# io-board-b-1.net
KiCad netlist of a schematic drawn in EAGLE
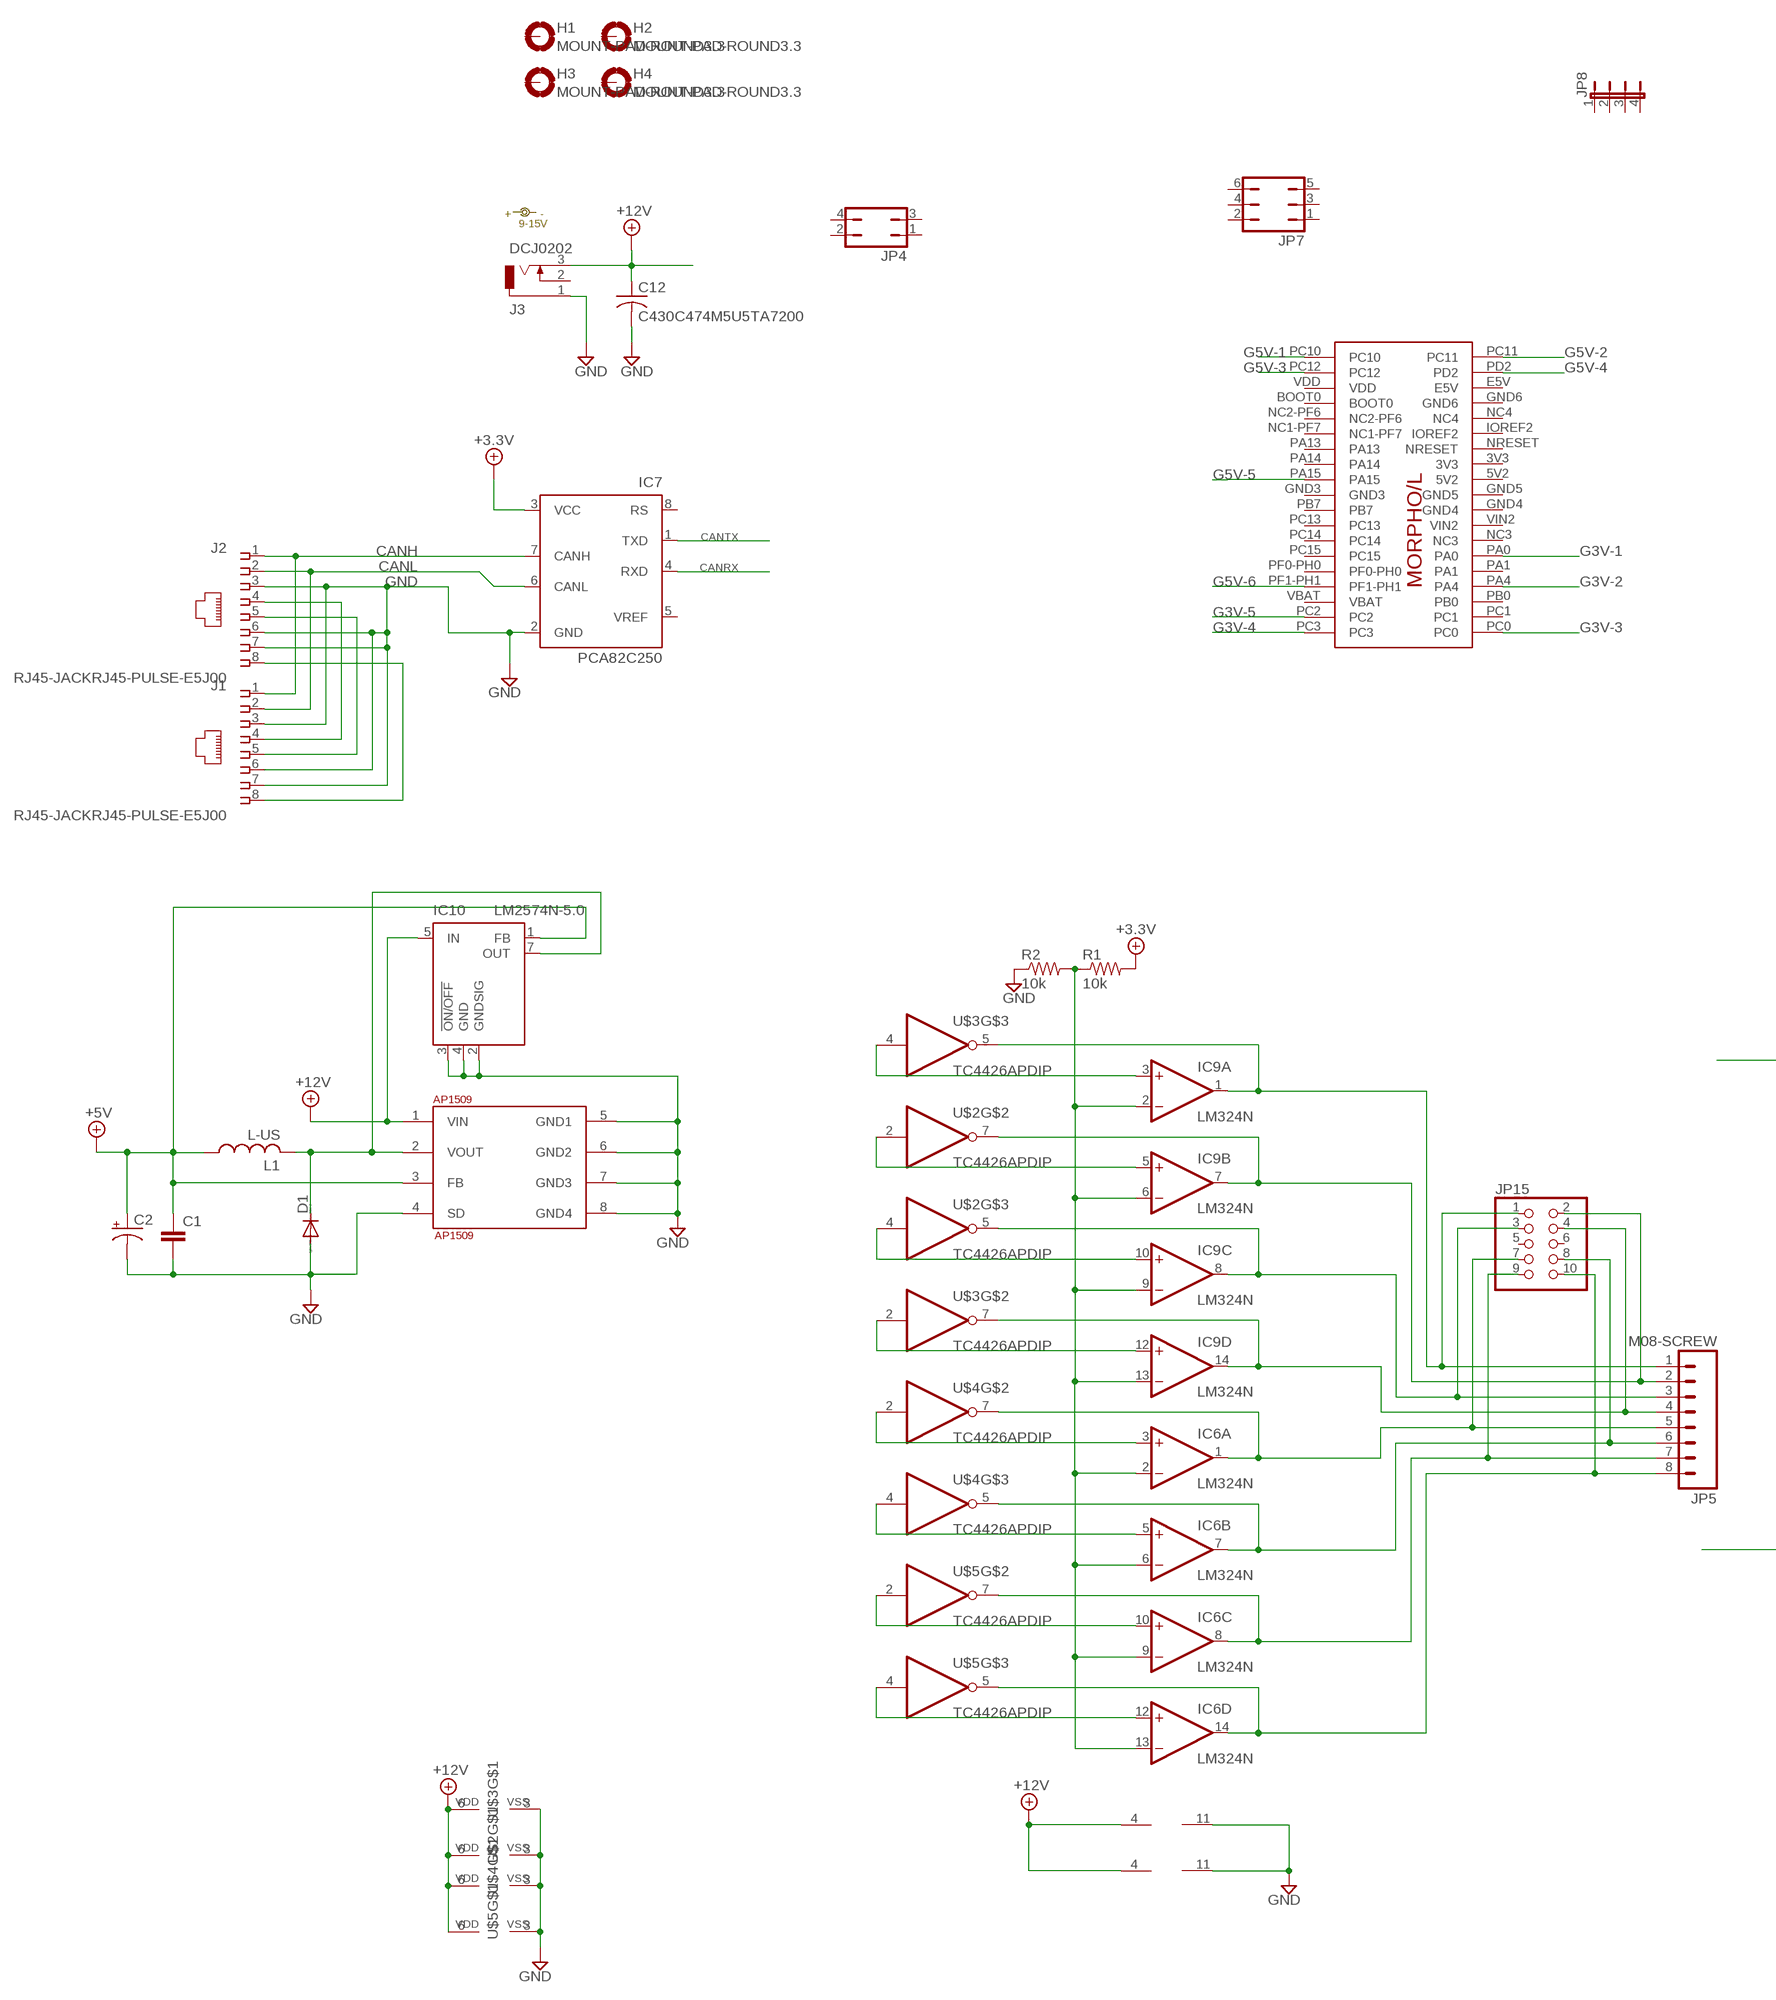
[diagram p0: schematic, sheet 1, part 1 of 2]
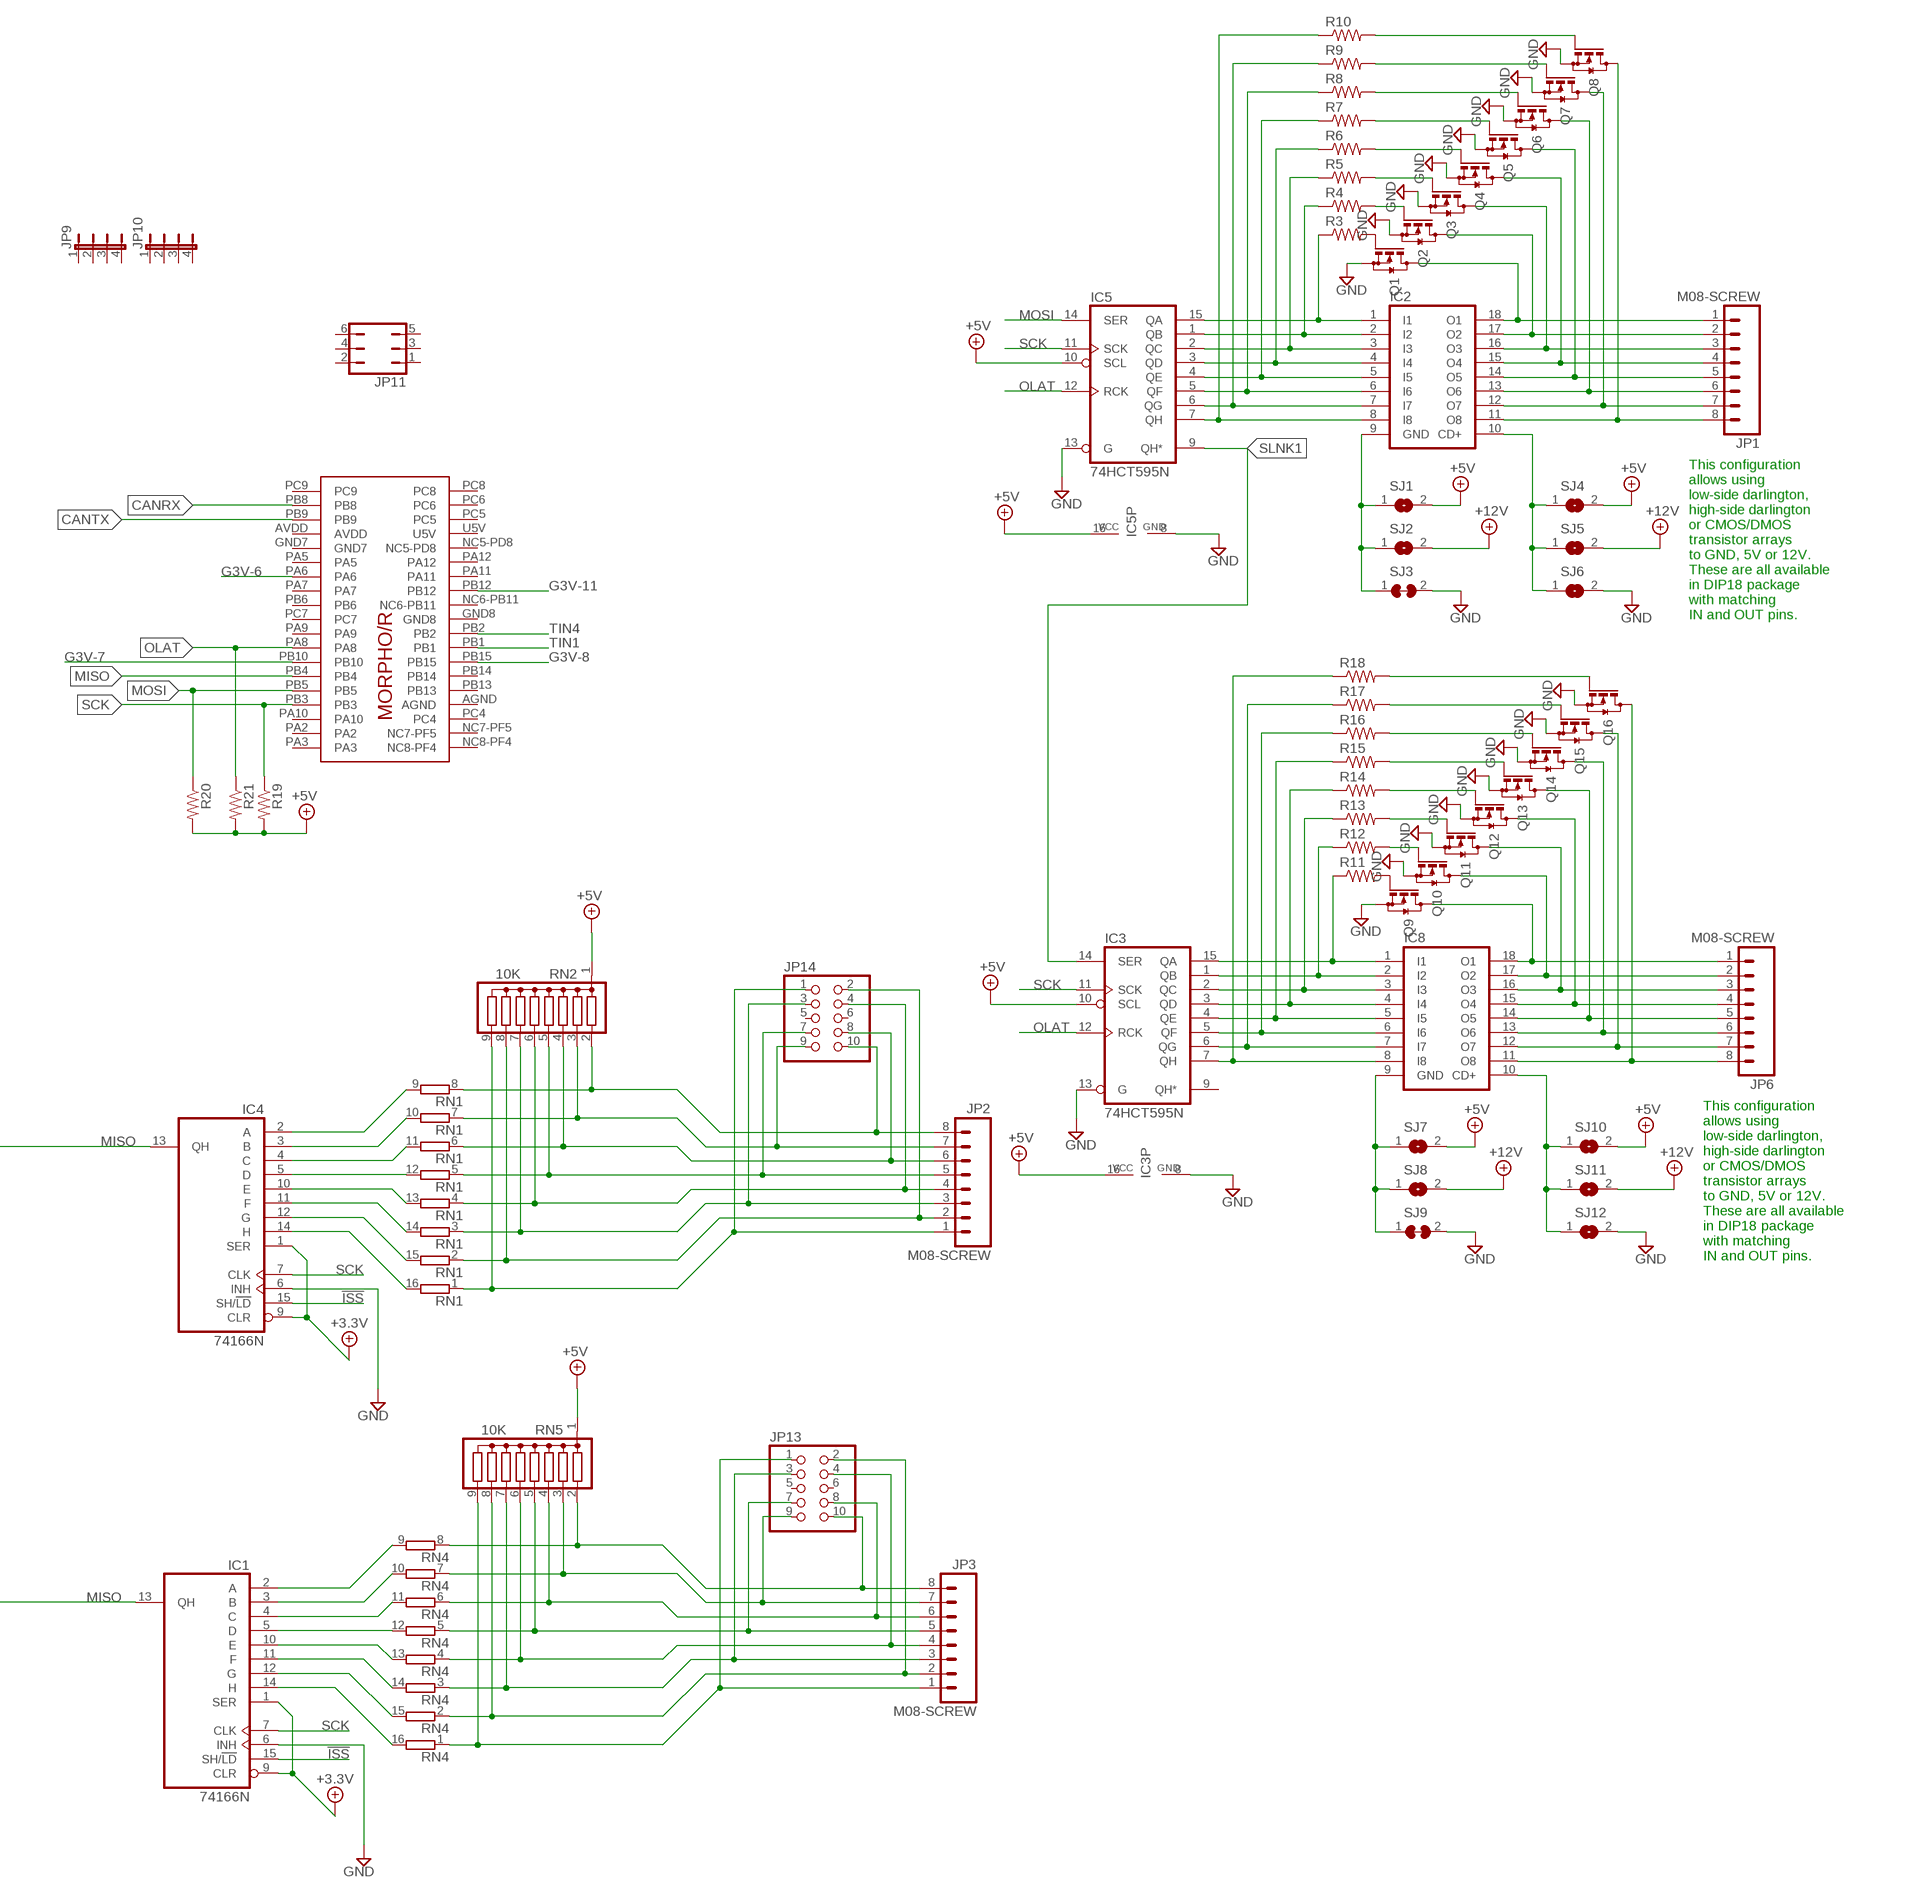
[diagram p1: schematic, sheet 1, part 2 of 2]

(export (version "E")
  (design (tool "Eeschema 10.0.6"))
  (components
    (comp (ref "+12V")
      (value "9-15V")
      (footprint "eagle-import:POWER_USAGE")
      (libsource (lib "eagle-import") (part "DOC-POWER_LABEL"))
    )
    (comp (ref "AP1509")
      (value "AP1509")
      (footprint "eagle-import:SO-08")
      (libsource (lib "eagle-import") (part "AP1509"))
    )
    (comp (ref "C1")
      (value "C-EUC1206")
      (footprint "eagle-import:C1206")
      (libsource (lib "eagle-import") (part "C-EUC1206"))
    )
    (comp (ref "C2")
      (value "CPOL-USE2.5-5")
      (footprint "eagle-import:E2,5-5")
      (libsource (lib "eagle-import") (part "CPOL-USE2.5-5"))
    )
    (comp (ref "C12")
      (value "C430C474M5U5TA7200")
      (footprint "eagle-import:C075-032X103")
      (libsource (lib "eagle-import") (part "C-US075-032X103"))
    )
    (comp (ref "D1")
      (value "DIODE-DO41-7.6")
      (footprint "eagle-import:DO41-7.6")
      (libsource (lib "eagle-import") (part "DIODE-DO41-7.6"))
    )
    (comp (ref "H1")
      (value "MOUNT-PAD-ROUND3.3")
      (footprint "eagle-import:3,3-PAD")
      (libsource (lib "eagle-import") (part "MOUNT-PAD-ROUND3.3"))
    )
    (comp (ref "H2")
      (value "MOUNT-PAD-ROUND3.3")
      (footprint "eagle-import:3,3-PAD")
      (libsource (lib "eagle-import") (part "MOUNT-PAD-ROUND3.3"))
    )
    (comp (ref "H3")
      (value "MOUNT-PAD-ROUND3.3")
      (footprint "eagle-import:3,3-PAD")
      (libsource (lib "eagle-import") (part "MOUNT-PAD-ROUND3.3"))
    )
    (comp (ref "H4")
      (value "MOUNT-PAD-ROUND3.3")
      (footprint "eagle-import:3,3-PAD")
      (libsource (lib "eagle-import") (part "MOUNT-PAD-ROUND3.3"))
    )
    (comp (ref "IC1")
      (value "74166N")
      (footprint "eagle-import:DIL16")
      (libsource (lib "eagle-import") (part "74166N"))
    )
    (comp (ref "IC2")
      (value "ULN2803A")
      (footprint "eagle-import:DIL18-THIN")
      (libsource (lib "eagle-import") (part "ULN2803A"))
    )
    (comp (ref "IC3")
      (value "74HCT595N")
      (footprint "eagle-import:DIL16")
      (libsource (lib "eagle-import") (part "74595NHCT"))
    )
    (comp (ref "IC4")
      (value "74166N")
      (footprint "eagle-import:DIL16")
      (libsource (lib "eagle-import") (part "74166N"))
    )
    (comp (ref "IC5")
      (value "74HCT595N")
      (footprint "eagle-import:DIL16")
      (libsource (lib "eagle-import") (part "74595NHCT"))
    )
    (comp (ref "IC6")
      (value "LM324N")
      (footprint "eagle-import:DIL14")
      (libsource (lib "eagle-import") (part "LM324N"))
    )
    (comp (ref "IC7")
      (value "PCA82C250")
      (footprint "eagle-import:DIL08")
      (libsource (lib "eagle-import") (part "PCA82C250"))
    )
    (comp (ref "IC8")
      (value "ULN2803A")
      (footprint "eagle-import:DIL18-THIN")
      (libsource (lib "eagle-import") (part "ULN2803A"))
    )
    (comp (ref "IC9")
      (value "LM324N")
      (footprint "eagle-import:DIL14")
      (libsource (lib "eagle-import") (part "LM324N"))
    )
    (comp (ref "IC10")
      (value "LM2574N-5.0")
      (footprint "eagle-import:DIL08")
      (libsource (lib "eagle-import") (part "LM2574?-N5.0"))
    )
    (comp (ref "J1")
      (value "RJ45-JACKRJ45-PULSE-E5J00")
      (footprint "eagle-import:RJ45-PULSE-E5J88")
      (libsource (lib "eagle-import") (part "RJ45-JACKRJ45-PULSE-E5J00"))
    )
    (comp (ref "J2")
      (value "RJ45-JACKRJ45-PULSE-E5J00")
      (footprint "eagle-import:RJ45-PULSE-E5J88")
      (libsource (lib "eagle-import") (part "RJ45-JACKRJ45-PULSE-E5J00"))
    )
    (comp (ref "J3")
      (value "DCJ0202")
      (footprint "eagle-import:DCJ0202")
      (libsource (lib "eagle-import") (part "DCJ0202"))
    )
    (comp (ref "JP1")
      (value "M08-SCREW")
      (footprint "eagle-import:1X08_TERMINAL")
      (libsource (lib "eagle-import") (part "M08-SCREW"))
    )
    (comp (ref "JP2")
      (value "M08-SCREW")
      (footprint "eagle-import:1X08_TERMINAL")
      (libsource (lib "eagle-import") (part "M08-SCREW"))
    )
    (comp (ref "JP3")
      (value "M08-SCREW")
      (footprint "eagle-import:1X08_TERMINAL")
      (libsource (lib "eagle-import") (part "M08-SCREW"))
    )
    (comp (ref "JP4")
      (value "JP2Q")
      (footprint "eagle-import:JP2Q")
      (libsource (lib "eagle-import") (part "JP2Q"))
    )
    (comp (ref "JP5")
      (value "M08-SCREW")
      (footprint "eagle-import:1X08_TERMINAL")
      (libsource (lib "eagle-import") (part "M08-SCREW"))
    )
    (comp (ref "JP6")
      (value "M08-SCREW")
      (footprint "eagle-import:1X08_TERMINAL")
      (libsource (lib "eagle-import") (part "M08-SCREW"))
    )
    (comp (ref "JP7")
      (value "JP3Q")
      (footprint "eagle-import:JP3Q")
      (libsource (lib "eagle-import") (part "JP3Q"))
    )
    (comp (ref "JP8")
      (value "JP4-FLAT")
      (footprint "eagle-import:JP4F")
      (libsource (lib "eagle-import") (part "JP4-FLAT"))
    )
    (comp (ref "JP9")
      (value "JP4-FLAT")
      (footprint "eagle-import:JP4F")
      (libsource (lib "eagle-import") (part "JP4-FLAT"))
    )
    (comp (ref "JP10")
      (value "JP4-FLAT")
      (footprint "eagle-import:JP4F")
      (libsource (lib "eagle-import") (part "JP4-FLAT"))
    )
    (comp (ref "JP11")
      (value "JP3Q")
      (footprint "eagle-import:JP3Q")
      (libsource (lib "eagle-import") (part "JP3Q"))
    )
    (comp (ref "JP13")
      (value "PINHD-2X5CN")
      (footprint "eagle-import:CON10M")
      (libsource (lib "eagle-import") (part "PINHD-2X5CN"))
    )
    (comp (ref "JP14")
      (value "PINHD-2X5CN")
      (footprint "eagle-import:CON10M")
      (libsource (lib "eagle-import") (part "PINHD-2X5CN"))
    )
    (comp (ref "JP15")
      (value "PINHD-2X5CN")
      (footprint "eagle-import:CON10M")
      (libsource (lib "eagle-import") (part "PINHD-2X5CN"))
    )
    (comp (ref "L1")
      (value "L-US")
      (footprint "eagle-import:L5-8,5")
      (libsource (lib "eagle-import") (part "L-US"))
    )
    (comp (ref "Q1")
      (value "BSS123")
      (footprint "eagle-import:SOT23")
      (libsource (lib "eagle-import") (part "BSS123"))
    )
    (comp (ref "Q2")
      (value "BSS123")
      (footprint "eagle-import:SOT23")
      (libsource (lib "eagle-import") (part "BSS123"))
    )
    (comp (ref "Q3")
      (value "BSS123")
      (footprint "eagle-import:SOT23")
      (libsource (lib "eagle-import") (part "BSS123"))
    )
    (comp (ref "Q4")
      (value "BSS123")
      (footprint "eagle-import:SOT23")
      (libsource (lib "eagle-import") (part "BSS123"))
    )
    (comp (ref "Q5")
      (value "BSS123")
      (footprint "eagle-import:SOT23")
      (libsource (lib "eagle-import") (part "BSS123"))
    )
    (comp (ref "Q6")
      (value "BSS123")
      (footprint "eagle-import:SOT23")
      (libsource (lib "eagle-import") (part "BSS123"))
    )
    (comp (ref "Q7")
      (value "BSS123")
      (footprint "eagle-import:SOT23")
      (libsource (lib "eagle-import") (part "BSS123"))
    )
    (comp (ref "Q8")
      (value "BSS123")
      (footprint "eagle-import:SOT23")
      (libsource (lib "eagle-import") (part "BSS123"))
    )
    (comp (ref "Q9")
      (value "BSS123")
      (footprint "eagle-import:SOT23")
      (libsource (lib "eagle-import") (part "BSS123"))
    )
    (comp (ref "Q10")
      (value "BSS123")
      (footprint "eagle-import:SOT23")
      (libsource (lib "eagle-import") (part "BSS123"))
    )
    (comp (ref "Q11")
      (value "BSS123")
      (footprint "eagle-import:SOT23")
      (libsource (lib "eagle-import") (part "BSS123"))
    )
    (comp (ref "Q12")
      (value "BSS123")
      (footprint "eagle-import:SOT23")
      (libsource (lib "eagle-import") (part "BSS123"))
    )
    (comp (ref "Q13")
      (value "BSS123")
      (footprint "eagle-import:SOT23")
      (libsource (lib "eagle-import") (part "BSS123"))
    )
    (comp (ref "Q14")
      (value "BSS123")
      (footprint "eagle-import:SOT23")
      (libsource (lib "eagle-import") (part "BSS123"))
    )
    (comp (ref "Q15")
      (value "BSS123")
      (footprint "eagle-import:SOT23")
      (libsource (lib "eagle-import") (part "BSS123"))
    )
    (comp (ref "Q16")
      (value "BSS123")
      (footprint "eagle-import:SOT23")
      (libsource (lib "eagle-import") (part "BSS123"))
    )
    (comp (ref "R1")
      (value "10k")
      (footprint "eagle-import:R1206")
      (libsource (lib "eagle-import") (part "R-US_R1206"))
    )
    (comp (ref "R2")
      (value "10k")
      (footprint "eagle-import:R1206")
      (libsource (lib "eagle-import") (part "R-US_R1206"))
    )
    (comp (ref "R3")
      (value "R-US_R0603")
      (footprint "eagle-import:R0603")
      (libsource (lib "eagle-import") (part "R-US_R0603"))
    )
    (comp (ref "R4")
      (value "R-US_R0603")
      (footprint "eagle-import:R0603")
      (libsource (lib "eagle-import") (part "R-US_R0603"))
    )
    (comp (ref "R5")
      (value "R-US_R0603")
      (footprint "eagle-import:R0603")
      (libsource (lib "eagle-import") (part "R-US_R0603"))
    )
    (comp (ref "R6")
      (value "R-US_R0603")
      (footprint "eagle-import:R0603")
      (libsource (lib "eagle-import") (part "R-US_R0603"))
    )
    (comp (ref "R7")
      (value "R-US_R0603")
      (footprint "eagle-import:R0603")
      (libsource (lib "eagle-import") (part "R-US_R0603"))
    )
    (comp (ref "R8")
      (value "R-US_R0603")
      (footprint "eagle-import:R0603")
      (libsource (lib "eagle-import") (part "R-US_R0603"))
    )
    (comp (ref "R9")
      (value "R-US_R0603")
      (footprint "eagle-import:R0603")
      (libsource (lib "eagle-import") (part "R-US_R0603"))
    )
    (comp (ref "R10")
      (value "R-US_R0603")
      (footprint "eagle-import:R0603")
      (libsource (lib "eagle-import") (part "R-US_R0603"))
    )
    (comp (ref "R11")
      (value "R-US_R0603")
      (footprint "eagle-import:R0603")
      (libsource (lib "eagle-import") (part "R-US_R0603"))
    )
    (comp (ref "R12")
      (value "R-US_R0603")
      (footprint "eagle-import:R0603")
      (libsource (lib "eagle-import") (part "R-US_R0603"))
    )
    (comp (ref "R13")
      (value "R-US_R0603")
      (footprint "eagle-import:R0603")
      (libsource (lib "eagle-import") (part "R-US_R0603"))
    )
    (comp (ref "R14")
      (value "R-US_R0603")
      (footprint "eagle-import:R0603")
      (libsource (lib "eagle-import") (part "R-US_R0603"))
    )
    (comp (ref "R15")
      (value "R-US_R0603")
      (footprint "eagle-import:R0603")
      (libsource (lib "eagle-import") (part "R-US_R0603"))
    )
    (comp (ref "R16")
      (value "R-US_R0603")
      (footprint "eagle-import:R0603")
      (libsource (lib "eagle-import") (part "R-US_R0603"))
    )
    (comp (ref "R17")
      (value "R-US_R0603")
      (footprint "eagle-import:R0603")
      (libsource (lib "eagle-import") (part "R-US_R0603"))
    )
    (comp (ref "R18")
      (value "R-US_R0603")
      (footprint "eagle-import:R0603")
      (libsource (lib "eagle-import") (part "R-US_R0603"))
    )
    (comp (ref "R19")
      (value "R-US_R0805")
      (footprint "eagle-import:R0805")
      (libsource (lib "eagle-import") (part "rcl_334_R-US_R0805"))
    )
    (comp (ref "R20")
      (value "R-US_R0805")
      (footprint "eagle-import:R0805")
      (libsource (lib "eagle-import") (part "rcl_334_R-US_R0805"))
    )
    (comp (ref "R21")
      (value "R-US_R0805")
      (footprint "eagle-import:R0805")
      (libsource (lib "eagle-import") (part "rcl_334_R-US_R0805"))
    )
    (comp (ref "RN1")
      (value "8R-P")
      (footprint "eagle-import:DIL16")
      (libsource (lib "eagle-import") (part "8R-P"))
    )
    (comp (ref "RN2")
      (value "10K")
      (footprint "eagle-import:SIL9")
      (libsource (lib "eagle-import") (part "G08R"))
    )
    (comp (ref "RN4")
      (value "8R-P")
      (footprint "eagle-import:DIL16")
      (libsource (lib "eagle-import") (part "8R-P"))
    )
    (comp (ref "RN5")
      (value "10K")
      (footprint "eagle-import:SIL9")
      (libsource (lib "eagle-import") (part "G08R"))
    )
    (comp (ref "SJ1")
      (value "SJ")
      (footprint "eagle-import:SJ-RND")
      (libsource (lib "eagle-import") (part "SJ"))
    )
    (comp (ref "SJ2")
      (value "SJ")
      (footprint "eagle-import:SJ-RND")
      (libsource (lib "eagle-import") (part "SJ"))
    )
    (comp (ref "SJ3")
      (value "SJ-C")
      (footprint "eagle-import:SJW-C")
      (libsource (lib "eagle-import") (part "SJ-C"))
    )
    (comp (ref "SJ4")
      (value "SJ")
      (footprint "eagle-import:SJ-RND")
      (libsource (lib "eagle-import") (part "SJ"))
    )
    (comp (ref "SJ5")
      (value "SJ")
      (footprint "eagle-import:SJ-RND")
      (libsource (lib "eagle-import") (part "SJ"))
    )
    (comp (ref "SJ6")
      (value "SJ")
      (footprint "eagle-import:SJ-RND")
      (libsource (lib "eagle-import") (part "SJ"))
    )
    (comp (ref "SJ7")
      (value "SJ")
      (footprint "eagle-import:SJ-RND")
      (libsource (lib "eagle-import") (part "SJ"))
    )
    (comp (ref "SJ8")
      (value "SJ")
      (footprint "eagle-import:SJ-RND")
      (libsource (lib "eagle-import") (part "SJ"))
    )
    (comp (ref "SJ9")
      (value "SJ-C")
      (footprint "eagle-import:SJW-C")
      (libsource (lib "eagle-import") (part "SJ-C"))
    )
    (comp (ref "SJ10")
      (value "SJ")
      (footprint "eagle-import:SJ-RND")
      (libsource (lib "eagle-import") (part "SJ"))
    )
    (comp (ref "SJ11")
      (value "SJ")
      (footprint "eagle-import:SJ-RND")
      (libsource (lib "eagle-import") (part "SJ"))
    )
    (comp (ref "SJ12")
      (value "SJ")
      (footprint "eagle-import:SJ-RND")
      (libsource (lib "eagle-import") (part "SJ"))
    )
    (comp (ref "U$1")
      (value "NUCLEO_64_GENERIC")
      (footprint "eagle-import:NUCLEO_BRD_BASE64")
      (libsource (lib "eagle-import") (part "NUCLEO_64_GENERIC"))
    )
    (comp (ref "U$2")
      (value "TC4426APDIP")
      (footprint "eagle-import:DIL08-LONG")
      (libsource (lib "eagle-import") (part "TC4426APDIP"))
    )
    (comp (ref "U$3")
      (value "TC4426APDIP")
      (footprint "eagle-import:DIL08-LONG")
      (libsource (lib "eagle-import") (part "TC4426APDIP"))
    )
    (comp (ref "U$4")
      (value "TC4426APDIP")
      (footprint "eagle-import:DIL08-LONG")
      (libsource (lib "eagle-import") (part "TC4426APDIP"))
    )
    (comp (ref "U$5")
      (value "TC4426APDIP")
      (footprint "eagle-import:DIL08-LONG")
      (libsource (lib "eagle-import") (part "TC4426APDIP"))
    )
  )
  (nets
    (net (code "1") (name "+3.3V") (class "Default")
      (node (ref "IC1") (pin "1") (pinfunction "SER_1") (pintype "input"))
      (node (ref "IC1") (pin "9") (pinfunction "CLR_9") (pintype "input"))
      (node (ref "IC4") (pin "1") (pinfunction "SER_1") (pintype "input"))
      (node (ref "IC4") (pin "9") (pinfunction "CLR_9") (pintype "input"))
      (node (ref "IC7") (pin "3") (pinfunction "VCC_3") (pintype "power_in"))
      (node (ref "R1") (pin "2") (pinfunction "2_2") (pintype "passive"))
    )
    (net (code "2") (name "+5V") (class "Default")
      (node (ref "AP1509") (pin "3") (pinfunction "FB_3") (pintype "bidirectional"))
      (node (ref "C1") (pin "1") (pinfunction "1_1") (pintype "passive"))
      (node (ref "C2") (pin "+") (pinfunction "+_+") (pintype "passive"))
      (node (ref "IC10") (pin "1") (pinfunction "FB_1") (pintype "input"))
      (node (ref "IC3") (pin "10") (pinfunction "SCL_10") (pintype "input"))
      (node (ref "IC3") (pin "16") (pinfunction "VCC_16") (pintype "power_in"))
      (node (ref "IC5") (pin "10") (pinfunction "SCL_10") (pintype "input"))
      (node (ref "IC5") (pin "16") (pinfunction "VCC_16") (pintype "power_in"))
      (node (ref "L1") (pin "1") (pinfunction "1_1") (pintype "passive"))
      (node (ref "R19") (pin "2") (pinfunction "2_2") (pintype "passive"))
      (node (ref "R20") (pin "2") (pinfunction "2_2") (pintype "passive"))
      (node (ref "R21") (pin "2") (pinfunction "2_2") (pintype "passive"))
      (node (ref "RN2") (pin "1") (pinfunction "1_1") (pintype "passive"))
      (node (ref "RN5") (pin "1") (pinfunction "1_1") (pintype "passive"))
      (node (ref "SJ1") (pin "2") (pinfunction "2_2") (pintype "passive"))
      (node (ref "SJ10") (pin "2") (pinfunction "2_2") (pintype "passive"))
      (node (ref "SJ4") (pin "2") (pinfunction "2_2") (pintype "passive"))
      (node (ref "SJ7") (pin "2") (pinfunction "2_2") (pintype "passive"))
    )
    (net (code "3") (name "+12V") (class "Default")
      (node (ref "AP1509") (pin "1") (pinfunction "VIN_1") (pintype "bidirectional"))
      (node (ref "C12") (pin "1") (pinfunction "1_1") (pintype "passive"))
      (node (ref "IC10") (pin "5") (pinfunction "IN_5") (pintype "input"))
      (node (ref "IC6") (pin "4") (pinfunction "V+_4") (pintype "power_in"))
      (node (ref "IC9") (pin "4") (pinfunction "V+_4") (pintype "power_in"))
      (node (ref "J3") (pin "3") (pinfunction "3_3") (pintype "passive"))
      (node (ref "SJ11") (pin "2") (pinfunction "2_2") (pintype "passive"))
      (node (ref "SJ2") (pin "2") (pinfunction "2_2") (pintype "passive"))
      (node (ref "SJ5") (pin "2") (pinfunction "2_2") (pintype "passive"))
      (node (ref "SJ8") (pin "2") (pinfunction "2_2") (pintype "passive"))
      (node (ref "U$2") (pin "6") (pinfunction "VDD_6") (pintype "power_in"))
      (node (ref "U$3") (pin "6") (pinfunction "VDD_6") (pintype "power_in"))
      (node (ref "U$4") (pin "6") (pinfunction "VDD_6") (pintype "power_in"))
      (node (ref "U$5") (pin "6") (pinfunction "VDD_6") (pintype "power_in"))
    )
    (net (code "4") (name "/3V3") (class "Default")
      (node (ref "U$1") (pin "3V3") (pinfunction "3V3_3V3") (pintype "power_in"))
    )
    (net (code "5") (name "/5V2") (class "Default")
      (node (ref "U$1") (pin "5V2") (pinfunction "5V2_5V2") (pintype "power_in"))
    )
    (net (code "6") (name "/AGND") (class "Default")
      (node (ref "U$1") (pin "AGND") (pinfunction "AGND_AGND") (pintype "power_in"))
    )
    (net (code "7") (name "/AVDD") (class "Default")
      (node (ref "U$1") (pin "AVDD") (pinfunction "AVDD_AVDD") (pintype "power_in"))
    )
    (net (code "8") (name "/CANH") (class "Default")
      (node (ref "IC7") (pin "7") (pinfunction "CANH_7") (pintype "bidirectional"))
      (node (ref "J1") (pin "1") (pinfunction "1_1") (pintype "passive"))
      (node (ref "J2") (pin "1") (pinfunction "1_1") (pintype "passive"))
    )
    (net (code "9") (name "/CANL") (class "Default")
      (node (ref "IC7") (pin "6") (pinfunction "CANL_6") (pintype "bidirectional"))
      (node (ref "J1") (pin "2") (pinfunction "2_2") (pintype "passive"))
      (node (ref "J2") (pin "2") (pinfunction "2_2") (pintype "passive"))
    )
    (net (code "10") (name "/E5V") (class "Default")
      (node (ref "U$1") (pin "E5V") (pinfunction "E5V_E5V") (pintype "power_in"))
    )
    (net (code "11") (name "/G3V-1") (class "Default")
      (node (ref "U$1") (pin "PA0") (pinfunction "PA0_PA0") (pintype "bidirectional"))
    )
    (net (code "12") (name "/G3V-2") (class "Default")
      (node (ref "U$1") (pin "PA4") (pinfunction "PA4_PA4") (pintype "bidirectional"))
    )
    (net (code "13") (name "/G3V-3") (class "Default")
      (node (ref "U$1") (pin "PC0") (pinfunction "PC0_PC0") (pintype "bidirectional"))
    )
    (net (code "14") (name "/G3V-4") (class "Default")
      (node (ref "U$1") (pin "PC3") (pinfunction "PC3_PC3") (pintype "bidirectional"))
    )
    (net (code "15") (name "/G3V-5") (class "Default")
      (node (ref "U$1") (pin "PC2") (pinfunction "PC2_PC2") (pintype "bidirectional"))
    )
    (net (code "16") (name "/G3V-6") (class "Default")
      (node (ref "U$1") (pin "PA6") (pinfunction "PA6_PA6") (pintype "bidirectional"))
    )
    (net (code "17") (name "/G3V-7") (class "Default")
      (node (ref "U$1") (pin "PB10") (pinfunction "PB10_PB10") (pintype "bidirectional"))
    )
    (net (code "18") (name "/G3V-8") (class "Default")
      (node (ref "U$1") (pin "PB15") (pinfunction "PB15_PB15") (pintype "bidirectional"))
    )
    (net (code "19") (name "/G3V-11") (class "Default")
      (node (ref "U$1") (pin "PB12") (pinfunction "PB12_PB12") (pintype "bidirectional"))
    )
    (net (code "20") (name "/G5V-1") (class "Default")
      (node (ref "U$1") (pin "PC10") (pinfunction "PC10_PC10") (pintype "bidirectional"))
    )
    (net (code "21") (name "/G5V-2") (class "Default")
      (node (ref "U$1") (pin "PC11") (pinfunction "PC11_PC11") (pintype "bidirectional"))
    )
    (net (code "22") (name "/G5V-3") (class "Default")
      (node (ref "U$1") (pin "PC12") (pinfunction "PC12_PC12") (pintype "bidirectional"))
    )
    (net (code "23") (name "/G5V-4") (class "Default")
      (node (ref "U$1") (pin "PD2") (pinfunction "PD2_PD2") (pintype "bidirectional"))
    )
    (net (code "24") (name "/G5V-5") (class "Default")
      (node (ref "U$1") (pin "PA15") (pinfunction "PA15_PA15") (pintype "bidirectional"))
    )
    (net (code "25") (name "/G5V-6") (class "Default")
      (node (ref "U$1") (pin "PF1-PH1") (pinfunction "PF1-PH1_PF1-PH1") (pintype "bidirectional"))
    )
    (net (code "26") (name "/GND3") (class "Default")
      (node (ref "U$1") (pin "GND3") (pinfunction "GND3_GND3") (pintype "power_in"))
    )
    (net (code "27") (name "/GND4") (class "Default")
      (node (ref "U$1") (pin "GND4") (pinfunction "GND4_GND4") (pintype "power_in"))
    )
    (net (code "28") (name "/GND5") (class "Default")
      (node (ref "U$1") (pin "GND5") (pinfunction "GND5_GND5") (pintype "power_in"))
    )
    (net (code "29") (name "/GND6") (class "Default")
      (node (ref "U$1") (pin "GND6") (pinfunction "GND6_GND6") (pintype "power_in"))
    )
    (net (code "30") (name "/GND7") (class "Default")
      (node (ref "U$1") (pin "GND7") (pinfunction "GND7_GND7") (pintype "power_in"))
    )
    (net (code "31") (name "/GND8") (class "Default")
      (node (ref "U$1") (pin "GND8") (pinfunction "GND8_GND8") (pintype "power_in"))
    )
    (net (code "32") (name "/TIN1") (class "Default")
      (node (ref "IC9") (pin "3") (pinfunction "+IN_3") (pintype "input"))
      (node (ref "U$1") (pin "PB1") (pinfunction "PB1_PB1") (pintype "bidirectional"))
      (node (ref "U$3") (pin "4") (pinfunction "I_4") (pintype "input"))
    )
    (net (code "33") (name "/TIN4") (class "Default")
      (node (ref "IC9") (pin "12") (pinfunction "+IN_12") (pintype "input"))
      (node (ref "U$1") (pin "PB2") (pinfunction "PB2_PB2") (pintype "bidirectional"))
      (node (ref "U$3") (pin "2") (pinfunction "I_2") (pintype "input"))
    )
    (net (code "34") (name "/U5V") (class "Default")
      (node (ref "U$1") (pin "U5V") (pinfunction "U5V_U5V") (pintype "power_in"))
    )
    (net (code "35") (name "/VBAT") (class "Default")
      (node (ref "U$1") (pin "VBAT") (pinfunction "VBAT_VBAT") (pintype "power_in"))
    )
    (net (code "36") (name "/VDD") (class "Default")
      (node (ref "U$1") (pin "VDD") (pinfunction "VDD_VDD") (pintype "power_in"))
    )
    (net (code "37") (name "/VIN2") (class "Default")
      (node (ref "U$1") (pin "VIN2") (pinfunction "VIN2_VIN2") (pintype "power_in"))
    )
    (net (code "38") (name "/~{ISS}") (class "Default")
      (node (ref "IC1") (pin "15") (pinfunction "SH/~{LD}_15") (pintype "input"))
      (node (ref "IC4") (pin "15") (pinfunction "SH/~{LD}_15") (pintype "input"))
    )
    (net (code "39") (name "CANRX") (class "Default")
      (node (ref "IC7") (pin "4") (pinfunction "RXD_4") (pintype "output"))
      (node (ref "U$1") (pin "PB8") (pinfunction "PB8_PB8") (pintype "bidirectional"))
    )
    (net (code "40") (name "CANTX") (class "Default")
      (node (ref "IC7") (pin "1") (pinfunction "TXD_1") (pintype "input"))
      (node (ref "U$1") (pin "PB9") (pinfunction "PB9_PB9") (pintype "bidirectional"))
    )
    (net (code "41") (name "GND") (class "Default")
      (node (ref "AP1509") (pin "4") (pinfunction "SD_4") (pintype "bidirectional"))
      (node (ref "AP1509") (pin "5") (pinfunction "GND1_5") (pintype "power_in"))
      (node (ref "AP1509") (pin "6") (pinfunction "GND2_6") (pintype "power_in"))
      (node (ref "AP1509") (pin "7") (pinfunction "GND3_7") (pintype "power_in"))
      (node (ref "AP1509") (pin "8") (pinfunction "GND4_8") (pintype "power_in"))
      (node (ref "C1") (pin "2") (pinfunction "2_2") (pintype "passive"))
      (node (ref "C12") (pin "2") (pinfunction "2_2") (pintype "passive"))
      (node (ref "C2") (pin "-") (pinfunction "-_-") (pintype "passive"))
      (node (ref "D1") (pin "A") (pinfunction "A_A") (pintype "passive"))
      (node (ref "IC1") (pin "6") (pinfunction "INH_6") (pintype "input"))
      (node (ref "IC10") (pin "2") (pinfunction "GNDSIG_2") (pintype "input"))
      (node (ref "IC10") (pin "3") (pinfunction "~{ON/OFF}_3") (pintype "input"))
      (node (ref "IC10") (pin "4") (pinfunction "GND_4") (pintype "power_in"))
      (node (ref "IC3") (pin "13") (pinfunction "G_13") (pintype "input"))
      (node (ref "IC3") (pin "8") (pinfunction "GND_8") (pintype "power_in"))
      (node (ref "IC4") (pin "6") (pinfunction "INH_6") (pintype "input"))
      (node (ref "IC5") (pin "13") (pinfunction "G_13") (pintype "input"))
      (node (ref "IC5") (pin "8") (pinfunction "GND_8") (pintype "power_in"))
      (node (ref "IC6") (pin "11") (pinfunction "V-_11") (pintype "power_in"))
      (node (ref "IC7") (pin "2") (pinfunction "GND_2") (pintype "power_in"))
      (node (ref "IC9") (pin "11") (pinfunction "V-_11") (pintype "power_in"))
      (node (ref "J1") (pin "3") (pinfunction "3_3") (pintype "passive"))
      (node (ref "J1") (pin "6") (pinfunction "6_6") (pintype "passive"))
      (node (ref "J1") (pin "7") (pinfunction "7_7") (pintype "passive"))
      (node (ref "J2") (pin "3") (pinfunction "3_3") (pintype "passive"))
      (node (ref "J2") (pin "6") (pinfunction "6_6") (pintype "passive"))
      (node (ref "J2") (pin "7") (pinfunction "7_7") (pintype "passive"))
      (node (ref "J3") (pin "1") (pinfunction "1_1") (pintype "passive"))
      (node (ref "Q1") (pin "2") (pinfunction "S_2") (pintype "passive"))
      (node (ref "Q10") (pin "2") (pinfunction "S_2") (pintype "passive"))
      (node (ref "Q11") (pin "2") (pinfunction "S_2") (pintype "passive"))
      (node (ref "Q12") (pin "2") (pinfunction "S_2") (pintype "passive"))
      (node (ref "Q13") (pin "2") (pinfunction "S_2") (pintype "passive"))
      (node (ref "Q14") (pin "2") (pinfunction "S_2") (pintype "passive"))
      (node (ref "Q15") (pin "2") (pinfunction "S_2") (pintype "passive"))
      (node (ref "Q16") (pin "2") (pinfunction "S_2") (pintype "passive"))
      (node (ref "Q2") (pin "2") (pinfunction "S_2") (pintype "passive"))
      (node (ref "Q3") (pin "2") (pinfunction "S_2") (pintype "passive"))
      (node (ref "Q4") (pin "2") (pinfunction "S_2") (pintype "passive"))
      (node (ref "Q5") (pin "2") (pinfunction "S_2") (pintype "passive"))
      (node (ref "Q6") (pin "2") (pinfunction "S_2") (pintype "passive"))
      (node (ref "Q7") (pin "2") (pinfunction "S_2") (pintype "passive"))
      (node (ref "Q8") (pin "2") (pinfunction "S_2") (pintype "passive"))
      (node (ref "Q9") (pin "2") (pinfunction "S_2") (pintype "passive"))
      (node (ref "R2") (pin "1") (pinfunction "1_1") (pintype "passive"))
      (node (ref "SJ12") (pin "2") (pinfunction "2_2") (pintype "passive"))
      (node (ref "SJ3") (pin "2") (pinfunction "2_2") (pintype "passive"))
      (node (ref "SJ6") (pin "2") (pinfunction "2_2") (pintype "passive"))
      (node (ref "SJ9") (pin "2") (pinfunction "2_2") (pintype "passive"))
      (node (ref "U$2") (pin "3") (pinfunction "VSS_3") (pintype "power_in"))
      (node (ref "U$3") (pin "3") (pinfunction "VSS_3") (pintype "power_in"))
      (node (ref "U$4") (pin "3") (pinfunction "VSS_3") (pintype "power_in"))
      (node (ref "U$5") (pin "3") (pinfunction "VSS_3") (pintype "power_in"))
    )
    (net (code "42") (name "MISO") (class "Default")
      (node (ref "IC1") (pin "13") (pinfunction "QH_13") (pintype "output"))
      (node (ref "IC4") (pin "13") (pinfunction "QH_13") (pintype "output"))
      (node (ref "U$1") (pin "PB4") (pinfunction "PB4_PB4") (pintype "bidirectional"))
    )
    (net (code "43") (name "MOSI") (class "Default")
      (node (ref "IC5") (pin "14") (pinfunction "SER_14") (pintype "input"))
      (node (ref "R20") (pin "1") (pinfunction "1_1") (pintype "passive"))
      (node (ref "U$1") (pin "PB5") (pinfunction "PB5_PB5") (pintype "bidirectional"))
    )
    (net (code "44") (name "Net-(AP1509-VOUT)") (class "Default")
      (node (ref "AP1509") (pin "2") (pinfunction "VOUT_2") (pintype "bidirectional"))
      (node (ref "D1") (pin "C") (pinfunction "C_C") (pintype "passive"))
      (node (ref "IC10") (pin "7") (pinfunction "OUT_7") (pintype "passive"))
      (node (ref "L1") (pin "2") (pinfunction "2_2") (pintype "passive"))
    )
    (net (code "45") (name "Net-(IC1A-A)") (class "Default")
      (node (ref "IC1") (pin "2") (pinfunction "A_2") (pintype "input"))
      (node (ref "RN4") (pin "9") (pinfunction "2_9") (pintype "passive"))
    )
    (net (code "46") (name "Net-(IC1A-B)") (class "Default")
      (node (ref "IC1") (pin "3") (pinfunction "B_3") (pintype "input"))
      (node (ref "RN4") (pin "10") (pinfunction "2_10") (pintype "passive"))
    )
    (net (code "47") (name "Net-(IC1A-C)") (class "Default")
      (node (ref "IC1") (pin "4") (pinfunction "C_4") (pintype "input"))
      (node (ref "RN4") (pin "11") (pinfunction "2_11") (pintype "passive"))
    )
    (net (code "48") (name "Net-(IC1A-D)") (class "Default")
      (node (ref "IC1") (pin "5") (pinfunction "D_5") (pintype "input"))
      (node (ref "RN4") (pin "12") (pinfunction "2_12") (pintype "passive"))
    )
    (net (code "49") (name "Net-(IC1A-E)") (class "Default")
      (node (ref "IC1") (pin "10") (pinfunction "E_10") (pintype "input"))
      (node (ref "RN4") (pin "13") (pinfunction "2_13") (pintype "passive"))
    )
    (net (code "50") (name "Net-(IC1A-F)") (class "Default")
      (node (ref "IC1") (pin "11") (pinfunction "F_11") (pintype "input"))
      (node (ref "RN4") (pin "14") (pinfunction "2_14") (pintype "passive"))
    )
    (net (code "51") (name "Net-(IC1A-G)") (class "Default")
      (node (ref "IC1") (pin "12") (pinfunction "G_12") (pintype "input"))
      (node (ref "RN4") (pin "15") (pinfunction "2_15") (pintype "passive"))
    )
    (net (code "52") (name "Net-(IC1A-H)") (class "Default")
      (node (ref "IC1") (pin "14") (pinfunction "H_14") (pintype "input"))
      (node (ref "RN4") (pin "16") (pinfunction "2_16") (pintype "passive"))
    )
    (net (code "53") (name "Net-(IC2-CD+)") (class "Default")
      (node (ref "IC2") (pin "10") (pinfunction "CD+_10") (pintype "passive"))
      (node (ref "SJ4") (pin "1") (pinfunction "1_1") (pintype "passive"))
      (node (ref "SJ5") (pin "1") (pinfunction "1_1") (pintype "passive"))
      (node (ref "SJ6") (pin "1") (pinfunction "1_1") (pintype "passive"))
    )
    (net (code "54") (name "Net-(IC2-GND)") (class "Default")
      (node (ref "IC2") (pin "9") (pinfunction "GND_9") (pintype "power_in"))
      (node (ref "SJ1") (pin "1") (pinfunction "1_1") (pintype "passive"))
      (node (ref "SJ2") (pin "1") (pinfunction "1_1") (pintype "passive"))
      (node (ref "SJ3") (pin "1") (pinfunction "1_1") (pintype "passive"))
    )
    (net (code "55") (name "Net-(IC2-I1)") (class "Default")
      (node (ref "IC2") (pin "1") (pinfunction "I1_1") (pintype "input"))
      (node (ref "IC5") (pin "15") (pinfunction "QA_15") (pintype "tri_state"))
      (node (ref "R3") (pin "1") (pinfunction "1_1") (pintype "passive"))
    )
    (net (code "56") (name "Net-(IC2-I2)") (class "Default")
      (node (ref "IC2") (pin "2") (pinfunction "I2_2") (pintype "input"))
      (node (ref "IC5") (pin "1") (pinfunction "QB_1") (pintype "tri_state"))
      (node (ref "R4") (pin "1") (pinfunction "1_1") (pintype "passive"))
    )
    (net (code "57") (name "Net-(IC2-I3)") (class "Default")
      (node (ref "IC2") (pin "3") (pinfunction "I3_3") (pintype "input"))
      (node (ref "IC5") (pin "2") (pinfunction "QC_2") (pintype "tri_state"))
      (node (ref "R5") (pin "1") (pinfunction "1_1") (pintype "passive"))
    )
    (net (code "58") (name "Net-(IC2-I4)") (class "Default")
      (node (ref "IC2") (pin "4") (pinfunction "I4_4") (pintype "input"))
      (node (ref "IC5") (pin "3") (pinfunction "QD_3") (pintype "tri_state"))
      (node (ref "R6") (pin "1") (pinfunction "1_1") (pintype "passive"))
    )
    (net (code "59") (name "Net-(IC2-I5)") (class "Default")
      (node (ref "IC2") (pin "5") (pinfunction "I5_5") (pintype "input"))
      (node (ref "IC5") (pin "4") (pinfunction "QE_4") (pintype "tri_state"))
      (node (ref "R7") (pin "1") (pinfunction "1_1") (pintype "passive"))
    )
    (net (code "60") (name "Net-(IC2-I6)") (class "Default")
      (node (ref "IC2") (pin "6") (pinfunction "I6_6") (pintype "input"))
      (node (ref "IC5") (pin "5") (pinfunction "QF_5") (pintype "tri_state"))
      (node (ref "R8") (pin "1") (pinfunction "1_1") (pintype "passive"))
    )
    (net (code "61") (name "Net-(IC2-I7)") (class "Default")
      (node (ref "IC2") (pin "7") (pinfunction "I7_7") (pintype "input"))
      (node (ref "IC5") (pin "6") (pinfunction "QG_6") (pintype "tri_state"))
      (node (ref "R9") (pin "1") (pinfunction "1_1") (pintype "passive"))
    )
    (net (code "62") (name "Net-(IC2-I8)") (class "Default")
      (node (ref "IC2") (pin "8") (pinfunction "I8_8") (pintype "input"))
      (node (ref "IC5") (pin "7") (pinfunction "QH_7") (pintype "tri_state"))
      (node (ref "R10") (pin "1") (pinfunction "1_1") (pintype "passive"))
    )
    (net (code "63") (name "Net-(IC2-O1)") (class "Default")
      (node (ref "IC2") (pin "18") (pinfunction "O1_18") (pintype "open_collector"))
      (node (ref "JP1") (pin "1") (pinfunction "1_1") (pintype "passive"))
      (node (ref "Q1") (pin "3") (pinfunction "D_3") (pintype "passive"))
    )
    (net (code "64") (name "Net-(IC2-O2)") (class "Default")
      (node (ref "IC2") (pin "17") (pinfunction "O2_17") (pintype "open_collector"))
      (node (ref "JP1") (pin "2") (pinfunction "2_2") (pintype "passive"))
      (node (ref "Q2") (pin "3") (pinfunction "D_3") (pintype "passive"))
    )
    (net (code "65") (name "Net-(IC2-O3)") (class "Default")
      (node (ref "IC2") (pin "16") (pinfunction "O3_16") (pintype "open_collector"))
      (node (ref "JP1") (pin "3") (pinfunction "3_3") (pintype "passive"))
      (node (ref "Q3") (pin "3") (pinfunction "D_3") (pintype "passive"))
    )
    (net (code "66") (name "Net-(IC2-O4)") (class "Default")
      (node (ref "IC2") (pin "15") (pinfunction "O4_15") (pintype "open_collector"))
      (node (ref "JP1") (pin "4") (pinfunction "4_4") (pintype "passive"))
      (node (ref "Q4") (pin "3") (pinfunction "D_3") (pintype "passive"))
    )
    (net (code "67") (name "Net-(IC2-O5)") (class "Default")
      (node (ref "IC2") (pin "14") (pinfunction "O5_14") (pintype "open_collector"))
      (node (ref "JP1") (pin "5") (pinfunction "5_5") (pintype "passive"))
      (node (ref "Q5") (pin "3") (pinfunction "D_3") (pintype "passive"))
    )
    (net (code "68") (name "Net-(IC2-O6)") (class "Default")
      (node (ref "IC2") (pin "13") (pinfunction "O6_13") (pintype "open_collector"))
      (node (ref "JP1") (pin "6") (pinfunction "6_6") (pintype "passive"))
      (node (ref "Q6") (pin "3") (pinfunction "D_3") (pintype "passive"))
    )
    (net (code "69") (name "Net-(IC2-O7)") (class "Default")
      (node (ref "IC2") (pin "12") (pinfunction "O7_12") (pintype "open_collector"))
      (node (ref "JP1") (pin "7") (pinfunction "7_7") (pintype "passive"))
      (node (ref "Q7") (pin "3") (pinfunction "D_3") (pintype "passive"))
    )
    (net (code "70") (name "Net-(IC2-O8)") (class "Default")
      (node (ref "IC2") (pin "11") (pinfunction "O8_11") (pintype "open_collector"))
      (node (ref "JP1") (pin "8") (pinfunction "8_8") (pintype "passive"))
      (node (ref "Q8") (pin "3") (pinfunction "D_3") (pintype "passive"))
    )
    (net (code "71") (name "Net-(IC3A-QA)") (class "Default")
      (node (ref "IC3") (pin "15") (pinfunction "QA_15") (pintype "tri_state"))
      (node (ref "IC8") (pin "1") (pinfunction "I1_1") (pintype "input"))
      (node (ref "R11") (pin "1") (pinfunction "1_1") (pintype "passive"))
    )
    (net (code "72") (name "Net-(IC3A-QB)") (class "Default")
      (node (ref "IC3") (pin "1") (pinfunction "QB_1") (pintype "tri_state"))
      (node (ref "IC8") (pin "2") (pinfunction "I2_2") (pintype "input"))
      (node (ref "R12") (pin "1") (pinfunction "1_1") (pintype "passive"))
    )
    (net (code "73") (name "Net-(IC3A-QC)") (class "Default")
      (node (ref "IC3") (pin "2") (pinfunction "QC_2") (pintype "tri_state"))
      (node (ref "IC8") (pin "3") (pinfunction "I3_3") (pintype "input"))
      (node (ref "R13") (pin "1") (pinfunction "1_1") (pintype "passive"))
    )
    (net (code "74") (name "Net-(IC3A-QD)") (class "Default")
      (node (ref "IC3") (pin "3") (pinfunction "QD_3") (pintype "tri_state"))
      (node (ref "IC8") (pin "4") (pinfunction "I4_4") (pintype "input"))
      (node (ref "R14") (pin "1") (pinfunction "1_1") (pintype "passive"))
    )
    (net (code "75") (name "Net-(IC3A-QE)") (class "Default")
      (node (ref "IC3") (pin "4") (pinfunction "QE_4") (pintype "tri_state"))
      (node (ref "IC8") (pin "5") (pinfunction "I5_5") (pintype "input"))
      (node (ref "R15") (pin "1") (pinfunction "1_1") (pintype "passive"))
    )
    (net (code "76") (name "Net-(IC3A-QF)") (class "Default")
      (node (ref "IC3") (pin "5") (pinfunction "QF_5") (pintype "tri_state"))
      (node (ref "IC8") (pin "6") (pinfunction "I6_6") (pintype "input"))
      (node (ref "R16") (pin "1") (pinfunction "1_1") (pintype "passive"))
    )
    (net (code "77") (name "Net-(IC3A-QG)") (class "Default")
      (node (ref "IC3") (pin "6") (pinfunction "QG_6") (pintype "tri_state"))
      (node (ref "IC8") (pin "7") (pinfunction "I7_7") (pintype "input"))
      (node (ref "R17") (pin "1") (pinfunction "1_1") (pintype "passive"))
    )
    (net (code "78") (name "Net-(IC3A-QH)") (class "Default")
      (node (ref "IC3") (pin "7") (pinfunction "QH_7") (pintype "tri_state"))
      (node (ref "IC8") (pin "8") (pinfunction "I8_8") (pintype "input"))
      (node (ref "R18") (pin "1") (pinfunction "1_1") (pintype "passive"))
    )
    (net (code "79") (name "Net-(IC4A-A)") (class "Default")
      (node (ref "IC4") (pin "2") (pinfunction "A_2") (pintype "input"))
      (node (ref "RN1") (pin "9") (pinfunction "2_9") (pintype "passive"))
    )
    (net (code "80") (name "Net-(IC4A-B)") (class "Default")
      (node (ref "IC4") (pin "3") (pinfunction "B_3") (pintype "input"))
      (node (ref "RN1") (pin "10") (pinfunction "2_10") (pintype "passive"))
    )
    (net (code "81") (name "Net-(IC4A-C)") (class "Default")
      (node (ref "IC4") (pin "4") (pinfunction "C_4") (pintype "input"))
      (node (ref "RN1") (pin "11") (pinfunction "2_11") (pintype "passive"))
    )
    (net (code "82") (name "Net-(IC4A-D)") (class "Default")
      (node (ref "IC4") (pin "5") (pinfunction "D_5") (pintype "input"))
      (node (ref "RN1") (pin "12") (pinfunction "2_12") (pintype "passive"))
    )
    (net (code "83") (name "Net-(IC4A-E)") (class "Default")
      (node (ref "IC4") (pin "10") (pinfunction "E_10") (pintype "input"))
      (node (ref "RN1") (pin "13") (pinfunction "2_13") (pintype "passive"))
    )
    (net (code "84") (name "Net-(IC4A-F)") (class "Default")
      (node (ref "IC4") (pin "11") (pinfunction "F_11") (pintype "input"))
      (node (ref "RN1") (pin "14") (pinfunction "2_14") (pintype "passive"))
    )
    (net (code "85") (name "Net-(IC4A-G)") (class "Default")
      (node (ref "IC4") (pin "12") (pinfunction "G_12") (pintype "input"))
      (node (ref "RN1") (pin "15") (pinfunction "2_15") (pintype "passive"))
    )
    (net (code "86") (name "Net-(IC4A-H)") (class "Default")
      (node (ref "IC4") (pin "14") (pinfunction "H_14") (pintype "input"))
      (node (ref "RN1") (pin "16") (pinfunction "2_16") (pintype "passive"))
    )
    (net (code "87") (name "Net-(IC6A-+IN)") (class "Default")
      (node (ref "IC6") (pin "3") (pinfunction "+IN_3") (pintype "input"))
      (node (ref "U$4") (pin "2") (pinfunction "I_2") (pintype "input"))
    )
    (net (code "88") (name "Net-(IC6A--IN)") (class "Default")
      (node (ref "IC6") (pin "13") (pinfunction "-IN_13") (pintype "input"))
      (node (ref "IC6") (pin "2") (pinfunction "-IN_2") (pintype "input"))
      (node (ref "IC6") (pin "6") (pinfunction "-IN_6") (pintype "input"))
      (node (ref "IC6") (pin "9") (pinfunction "-IN_9") (pintype "input"))
      (node (ref "IC9") (pin "13") (pinfunction "-IN_13") (pintype "input"))
      (node (ref "IC9") (pin "2") (pinfunction "-IN_2") (pintype "input"))
      (node (ref "IC9") (pin "6") (pinfunction "-IN_6") (pintype "input"))
      (node (ref "IC9") (pin "9") (pinfunction "-IN_9") (pintype "input"))
      (node (ref "R1") (pin "1") (pinfunction "1_1") (pintype "passive"))
      (node (ref "R2") (pin "2") (pinfunction "2_2") (pintype "passive"))
    )
    (net (code "89") (name "Net-(IC6A-OUT)") (class "Default")
      (node (ref "IC6") (pin "1") (pinfunction "OUT_1") (pintype "output"))
      (node (ref "JP15") (pin "7") (pinfunction "7_7") (pintype "passive"))
      (node (ref "JP5") (pin "5") (pinfunction "5_5") (pintype "passive"))
      (node (ref "U$4") (pin "7") (pinfunction "O_7") (pintype "output"))
    )
    (net (code "90") (name "Net-(IC6B-+IN)") (class "Default")
      (node (ref "IC6") (pin "5") (pinfunction "+IN_5") (pintype "input"))
      (node (ref "U$4") (pin "4") (pinfunction "I_4") (pintype "input"))
    )
    (net (code "91") (name "Net-(IC6B-OUT)") (class "Default")
      (node (ref "IC6") (pin "7") (pinfunction "OUT_7") (pintype "output"))
      (node (ref "JP15") (pin "8") (pinfunction "8_8") (pintype "passive"))
      (node (ref "JP5") (pin "6") (pinfunction "6_6") (pintype "passive"))
      (node (ref "U$4") (pin "5") (pinfunction "O_5") (pintype "output"))
    )
    (net (code "92") (name "Net-(IC6C-+IN)") (class "Default")
      (node (ref "IC6") (pin "10") (pinfunction "+IN_10") (pintype "input"))
      (node (ref "U$5") (pin "2") (pinfunction "I_2") (pintype "input"))
    )
    (net (code "93") (name "Net-(IC6C-OUT)") (class "Default")
      (node (ref "IC6") (pin "8") (pinfunction "OUT_8") (pintype "output"))
      (node (ref "JP15") (pin "9") (pinfunction "9_9") (pintype "passive"))
      (node (ref "JP5") (pin "7") (pinfunction "7_7") (pintype "passive"))
      (node (ref "U$5") (pin "7") (pinfunction "O_7") (pintype "output"))
    )
    (net (code "94") (name "Net-(IC6D-+IN)") (class "Default")
      (node (ref "IC6") (pin "12") (pinfunction "+IN_12") (pintype "input"))
      (node (ref "U$5") (pin "4") (pinfunction "I_4") (pintype "input"))
    )
    (net (code "95") (name "Net-(IC6D-OUT)") (class "Default")
      (node (ref "IC6") (pin "14") (pinfunction "OUT_14") (pintype "output"))
      (node (ref "JP15") (pin "10") (pinfunction "10_10") (pintype "passive"))
      (node (ref "JP5") (pin "8") (pinfunction "8_8") (pintype "passive"))
      (node (ref "U$5") (pin "5") (pinfunction "O_5") (pintype "output"))
    )
    (net (code "96") (name "Net-(IC8-CD+)") (class "Default")
      (node (ref "IC8") (pin "10") (pinfunction "CD+_10") (pintype "passive"))
      (node (ref "SJ10") (pin "1") (pinfunction "1_1") (pintype "passive"))
      (node (ref "SJ11") (pin "1") (pinfunction "1_1") (pintype "passive"))
      (node (ref "SJ12") (pin "1") (pinfunction "1_1") (pintype "passive"))
    )
    (net (code "97") (name "Net-(IC8-GND)") (class "Default")
      (node (ref "IC8") (pin "9") (pinfunction "GND_9") (pintype "power_in"))
      (node (ref "SJ7") (pin "1") (pinfunction "1_1") (pintype "passive"))
      (node (ref "SJ8") (pin "1") (pinfunction "1_1") (pintype "passive"))
      (node (ref "SJ9") (pin "1") (pinfunction "1_1") (pintype "passive"))
    )
    (net (code "98") (name "Net-(IC8-O1)") (class "Default")
      (node (ref "IC8") (pin "18") (pinfunction "O1_18") (pintype "open_collector"))
      (node (ref "JP6") (pin "1") (pinfunction "1_1") (pintype "passive"))
      (node (ref "Q9") (pin "3") (pinfunction "D_3") (pintype "passive"))
    )
    (net (code "99") (name "Net-(IC8-O2)") (class "Default")
      (node (ref "IC8") (pin "17") (pinfunction "O2_17") (pintype "open_collector"))
      (node (ref "JP6") (pin "2") (pinfunction "2_2") (pintype "passive"))
      (node (ref "Q10") (pin "3") (pinfunction "D_3") (pintype "passive"))
    )
    (net (code "100") (name "Net-(IC8-O3)") (class "Default")
      (node (ref "IC8") (pin "16") (pinfunction "O3_16") (pintype "open_collector"))
      (node (ref "JP6") (pin "3") (pinfunction "3_3") (pintype "passive"))
      (node (ref "Q11") (pin "3") (pinfunction "D_3") (pintype "passive"))
    )
    (net (code "101") (name "Net-(IC8-O4)") (class "Default")
      (node (ref "IC8") (pin "15") (pinfunction "O4_15") (pintype "open_collector"))
      (node (ref "JP6") (pin "4") (pinfunction "4_4") (pintype "passive"))
      (node (ref "Q12") (pin "3") (pinfunction "D_3") (pintype "passive"))
    )
    (net (code "102") (name "Net-(IC8-O5)") (class "Default")
      (node (ref "IC8") (pin "14") (pinfunction "O5_14") (pintype "open_collector"))
      (node (ref "JP6") (pin "5") (pinfunction "5_5") (pintype "passive"))
      (node (ref "Q13") (pin "3") (pinfunction "D_3") (pintype "passive"))
    )
    (net (code "103") (name "Net-(IC8-O6)") (class "Default")
      (node (ref "IC8") (pin "13") (pinfunction "O6_13") (pintype "open_collector"))
      (node (ref "JP6") (pin "6") (pinfunction "6_6") (pintype "passive"))
      (node (ref "Q14") (pin "3") (pinfunction "D_3") (pintype "passive"))
    )
    (net (code "104") (name "Net-(IC8-O7)") (class "Default")
      (node (ref "IC8") (pin "12") (pinfunction "O7_12") (pintype "open_collector"))
      (node (ref "JP6") (pin "7") (pinfunction "7_7") (pintype "passive"))
      (node (ref "Q15") (pin "3") (pinfunction "D_3") (pintype "passive"))
    )
    (net (code "105") (name "Net-(IC8-O8)") (class "Default")
      (node (ref "IC8") (pin "11") (pinfunction "O8_11") (pintype "open_collector"))
      (node (ref "JP6") (pin "8") (pinfunction "8_8") (pintype "passive"))
      (node (ref "Q16") (pin "3") (pinfunction "D_3") (pintype "passive"))
    )
    (net (code "106") (name "Net-(IC9A-OUT)") (class "Default")
      (node (ref "IC9") (pin "1") (pinfunction "OUT_1") (pintype "output"))
      (node (ref "JP15") (pin "1") (pinfunction "1_1") (pintype "passive"))
      (node (ref "JP5") (pin "1") (pinfunction "1_1") (pintype "passive"))
      (node (ref "U$3") (pin "5") (pinfunction "O_5") (pintype "output"))
    )
    (net (code "107") (name "Net-(IC9B-+IN)") (class "Default")
      (node (ref "IC9") (pin "5") (pinfunction "+IN_5") (pintype "input"))
      (node (ref "U$2") (pin "2") (pinfunction "I_2") (pintype "input"))
    )
    (net (code "108") (name "Net-(IC9B-OUT)") (class "Default")
      (node (ref "IC9") (pin "7") (pinfunction "OUT_7") (pintype "output"))
      (node (ref "JP15") (pin "2") (pinfunction "2_2") (pintype "passive"))
      (node (ref "JP5") (pin "2") (pinfunction "2_2") (pintype "passive"))
      (node (ref "U$2") (pin "7") (pinfunction "O_7") (pintype "output"))
    )
    (net (code "109") (name "Net-(IC9C-+IN)") (class "Default")
      (node (ref "IC9") (pin "10") (pinfunction "+IN_10") (pintype "input"))
      (node (ref "U$2") (pin "4") (pinfunction "I_4") (pintype "input"))
    )
    (net (code "110") (name "Net-(IC9C-OUT)") (class "Default")
      (node (ref "IC9") (pin "8") (pinfunction "OUT_8") (pintype "output"))
      (node (ref "JP15") (pin "3") (pinfunction "3_3") (pintype "passive"))
      (node (ref "JP5") (pin "3") (pinfunction "3_3") (pintype "passive"))
      (node (ref "U$2") (pin "5") (pinfunction "O_5") (pintype "output"))
    )
    (net (code "111") (name "Net-(IC9D-OUT)") (class "Default")
      (node (ref "IC9") (pin "14") (pinfunction "OUT_14") (pintype "output"))
      (node (ref "JP15") (pin "4") (pinfunction "4_4") (pintype "passive"))
      (node (ref "JP5") (pin "4") (pinfunction "4_4") (pintype "passive"))
      (node (ref "U$3") (pin "7") (pinfunction "O_7") (pintype "output"))
    )
    (net (code "112") (name "Net-(J1-Pad4)") (class "Default")
      (node (ref "J1") (pin "4") (pinfunction "4_4") (pintype "passive"))
      (node (ref "J2") (pin "4") (pinfunction "4_4") (pintype "passive"))
    )
    (net (code "113") (name "Net-(J1-Pad5)") (class "Default")
      (node (ref "J1") (pin "5") (pinfunction "5_5") (pintype "passive"))
      (node (ref "J2") (pin "5") (pinfunction "5_5") (pintype "passive"))
    )
    (net (code "114") (name "Net-(J1-Pad8)") (class "Default")
      (node (ref "J1") (pin "8") (pinfunction "8_8") (pintype "passive"))
      (node (ref "J2") (pin "8") (pinfunction "8_8") (pintype "passive"))
    )
    (net (code "115") (name "Net-(JP13-Pad1)") (class "Default")
      (node (ref "JP13") (pin "1") (pinfunction "1_1") (pintype "passive"))
      (node (ref "JP3") (pin "1") (pinfunction "1_1") (pintype "passive"))
      (node (ref "RN4") (pin "1") (pinfunction "1_1") (pintype "passive"))
      (node (ref "RN5") (pin "9") (pinfunction "9_9") (pintype "passive"))
    )
    (net (code "116") (name "Net-(JP14-Pad1)") (class "Default")
      (node (ref "JP14") (pin "1") (pinfunction "1_1") (pintype "passive"))
      (node (ref "JP2") (pin "1") (pinfunction "1_1") (pintype "passive"))
      (node (ref "RN1") (pin "1") (pinfunction "1_1") (pintype "passive"))
      (node (ref "RN2") (pin "9") (pinfunction "9_9") (pintype "passive"))
    )
    (net (code "117") (name "Net-(Q1-G)") (class "Default")
      (node (ref "Q1") (pin "1") (pinfunction "G_1") (pintype "passive"))
      (node (ref "R3") (pin "2") (pinfunction "2_2") (pintype "passive"))
    )
    (net (code "118") (name "Net-(Q2-G)") (class "Default")
      (node (ref "Q2") (pin "1") (pinfunction "G_1") (pintype "passive"))
      (node (ref "R4") (pin "2") (pinfunction "2_2") (pintype "passive"))
    )
    (net (code "119") (name "Net-(Q3-G)") (class "Default")
      (node (ref "Q3") (pin "1") (pinfunction "G_1") (pintype "passive"))
      (node (ref "R5") (pin "2") (pinfunction "2_2") (pintype "passive"))
    )
    (net (code "120") (name "Net-(Q4-G)") (class "Default")
      (node (ref "Q4") (pin "1") (pinfunction "G_1") (pintype "passive"))
      (node (ref "R6") (pin "2") (pinfunction "2_2") (pintype "passive"))
    )
    (net (code "121") (name "Net-(Q5-G)") (class "Default")
      (node (ref "Q5") (pin "1") (pinfunction "G_1") (pintype "passive"))
      (node (ref "R7") (pin "2") (pinfunction "2_2") (pintype "passive"))
    )
    (net (code "122") (name "Net-(Q6-G)") (class "Default")
      (node (ref "Q6") (pin "1") (pinfunction "G_1") (pintype "passive"))
      (node (ref "R8") (pin "2") (pinfunction "2_2") (pintype "passive"))
    )
    (net (code "123") (name "Net-(Q7-G)") (class "Default")
      (node (ref "Q7") (pin "1") (pinfunction "G_1") (pintype "passive"))
      (node (ref "R9") (pin "2") (pinfunction "2_2") (pintype "passive"))
    )
    (net (code "124") (name "Net-(Q8-G)") (class "Default")
      (node (ref "Q8") (pin "1") (pinfunction "G_1") (pintype "passive"))
      (node (ref "R10") (pin "2") (pinfunction "2_2") (pintype "passive"))
    )
    (net (code "125") (name "Net-(Q9-G)") (class "Default")
      (node (ref "Q9") (pin "1") (pinfunction "G_1") (pintype "passive"))
      (node (ref "R11") (pin "2") (pinfunction "2_2") (pintype "passive"))
    )
    (net (code "126") (name "Net-(Q10-G)") (class "Default")
      (node (ref "Q10") (pin "1") (pinfunction "G_1") (pintype "passive"))
      (node (ref "R12") (pin "2") (pinfunction "2_2") (pintype "passive"))
    )
    (net (code "127") (name "Net-(Q11-G)") (class "Default")
      (node (ref "Q11") (pin "1") (pinfunction "G_1") (pintype "passive"))
      (node (ref "R13") (pin "2") (pinfunction "2_2") (pintype "passive"))
    )
    (net (code "128") (name "Net-(Q12-G)") (class "Default")
      (node (ref "Q12") (pin "1") (pinfunction "G_1") (pintype "passive"))
      (node (ref "R14") (pin "2") (pinfunction "2_2") (pintype "passive"))
    )
    (net (code "129") (name "Net-(Q13-G)") (class "Default")
      (node (ref "Q13") (pin "1") (pinfunction "G_1") (pintype "passive"))
      (node (ref "R15") (pin "2") (pinfunction "2_2") (pintype "passive"))
    )
    (net (code "130") (name "Net-(Q14-G)") (class "Default")
      (node (ref "Q14") (pin "1") (pinfunction "G_1") (pintype "passive"))
      (node (ref "R16") (pin "2") (pinfunction "2_2") (pintype "passive"))
    )
    (net (code "131") (name "Net-(Q15-G)") (class "Default")
      (node (ref "Q15") (pin "1") (pinfunction "G_1") (pintype "passive"))
      (node (ref "R17") (pin "2") (pinfunction "2_2") (pintype "passive"))
    )
    (net (code "132") (name "Net-(Q16-G)") (class "Default")
      (node (ref "Q16") (pin "1") (pinfunction "G_1") (pintype "passive"))
      (node (ref "R18") (pin "2") (pinfunction "2_2") (pintype "passive"))
    )
    (net (code "133") (name "Net-(RN1B-1)") (class "Default")
      (node (ref "JP14") (pin "2") (pinfunction "2_2") (pintype "passive"))
      (node (ref "JP2") (pin "2") (pinfunction "2_2") (pintype "passive"))
      (node (ref "RN1") (pin "2") (pinfunction "1_2") (pintype "passive"))
      (node (ref "RN2") (pin "8") (pinfunction "8_8") (pintype "passive"))
    )
    (net (code "134") (name "Net-(RN1C-1)") (class "Default")
      (node (ref "JP14") (pin "3") (pinfunction "3_3") (pintype "passive"))
      (node (ref "JP2") (pin "3") (pinfunction "3_3") (pintype "passive"))
      (node (ref "RN1") (pin "3") (pinfunction "1_3") (pintype "passive"))
      (node (ref "RN2") (pin "7") (pinfunction "7_7") (pintype "passive"))
    )
    (net (code "135") (name "Net-(RN1D-1)") (class "Default")
      (node (ref "JP14") (pin "4") (pinfunction "4_4") (pintype "passive"))
      (node (ref "JP2") (pin "4") (pinfunction "4_4") (pintype "passive"))
      (node (ref "RN1") (pin "4") (pinfunction "1_4") (pintype "passive"))
      (node (ref "RN2") (pin "6") (pinfunction "6_6") (pintype "passive"))
    )
    (net (code "136") (name "Net-(RN1E-1)") (class "Default")
      (node (ref "JP14") (pin "7") (pinfunction "7_7") (pintype "passive"))
      (node (ref "JP2") (pin "5") (pinfunction "5_5") (pintype "passive"))
      (node (ref "RN1") (pin "5") (pinfunction "1_5") (pintype "passive"))
      (node (ref "RN2") (pin "5") (pinfunction "5_5") (pintype "passive"))
    )
    (net (code "137") (name "Net-(RN1F-1)") (class "Default")
      (node (ref "JP14") (pin "8") (pinfunction "8_8") (pintype "passive"))
      (node (ref "JP2") (pin "6") (pinfunction "6_6") (pintype "passive"))
      (node (ref "RN1") (pin "6") (pinfunction "1_6") (pintype "passive"))
      (node (ref "RN2") (pin "4") (pinfunction "4_4") (pintype "passive"))
    )
    (net (code "138") (name "Net-(RN1G-1)") (class "Default")
      (node (ref "JP14") (pin "9") (pinfunction "9_9") (pintype "passive"))
      (node (ref "JP2") (pin "7") (pinfunction "7_7") (pintype "passive"))
      (node (ref "RN1") (pin "7") (pinfunction "1_7") (pintype "passive"))
      (node (ref "RN2") (pin "3") (pinfunction "3_3") (pintype "passive"))
    )
    (net (code "139") (name "Net-(RN1H-1)") (class "Default")
      (node (ref "JP14") (pin "10") (pinfunction "10_10") (pintype "passive"))
      (node (ref "JP2") (pin "8") (pinfunction "8_8") (pintype "passive"))
      (node (ref "RN1") (pin "8") (pinfunction "1_8") (pintype "passive"))
      (node (ref "RN2") (pin "2") (pinfunction "2_2") (pintype "passive"))
    )
    (net (code "140") (name "Net-(RN4B-1)") (class "Default")
      (node (ref "JP13") (pin "2") (pinfunction "2_2") (pintype "passive"))
      (node (ref "JP3") (pin "2") (pinfunction "2_2") (pintype "passive"))
      (node (ref "RN4") (pin "2") (pinfunction "1_2") (pintype "passive"))
      (node (ref "RN5") (pin "8") (pinfunction "8_8") (pintype "passive"))
    )
    (net (code "141") (name "Net-(RN4C-1)") (class "Default")
      (node (ref "JP13") (pin "3") (pinfunction "3_3") (pintype "passive"))
      (node (ref "JP3") (pin "3") (pinfunction "3_3") (pintype "passive"))
      (node (ref "RN4") (pin "3") (pinfunction "1_3") (pintype "passive"))
      (node (ref "RN5") (pin "7") (pinfunction "7_7") (pintype "passive"))
    )
    (net (code "142") (name "Net-(RN4D-1)") (class "Default")
      (node (ref "JP13") (pin "4") (pinfunction "4_4") (pintype "passive"))
      (node (ref "JP3") (pin "4") (pinfunction "4_4") (pintype "passive"))
      (node (ref "RN4") (pin "4") (pinfunction "1_4") (pintype "passive"))
      (node (ref "RN5") (pin "6") (pinfunction "6_6") (pintype "passive"))
    )
    (net (code "143") (name "Net-(RN4E-1)") (class "Default")
      (node (ref "JP13") (pin "7") (pinfunction "7_7") (pintype "passive"))
      (node (ref "JP3") (pin "5") (pinfunction "5_5") (pintype "passive"))
      (node (ref "RN4") (pin "5") (pinfunction "1_5") (pintype "passive"))
      (node (ref "RN5") (pin "5") (pinfunction "5_5") (pintype "passive"))
    )
    (net (code "144") (name "Net-(RN4F-1)") (class "Default")
      (node (ref "JP13") (pin "8") (pinfunction "8_8") (pintype "passive"))
      (node (ref "JP3") (pin "6") (pinfunction "6_6") (pintype "passive"))
      (node (ref "RN4") (pin "6") (pinfunction "1_6") (pintype "passive"))
      (node (ref "RN5") (pin "4") (pinfunction "4_4") (pintype "passive"))
    )
    (net (code "145") (name "Net-(RN4G-1)") (class "Default")
      (node (ref "JP13") (pin "9") (pinfunction "9_9") (pintype "passive"))
      (node (ref "JP3") (pin "7") (pinfunction "7_7") (pintype "passive"))
      (node (ref "RN4") (pin "7") (pinfunction "1_7") (pintype "passive"))
      (node (ref "RN5") (pin "3") (pinfunction "3_3") (pintype "passive"))
    )
    (net (code "146") (name "Net-(RN4H-1)") (class "Default")
      (node (ref "JP13") (pin "10") (pinfunction "10_10") (pintype "passive"))
      (node (ref "JP3") (pin "8") (pinfunction "8_8") (pintype "passive"))
      (node (ref "RN4") (pin "8") (pinfunction "1_8") (pintype "passive"))
      (node (ref "RN5") (pin "2") (pinfunction "2_2") (pintype "passive"))
    )
    (net (code "147") (name "OLAT") (class "Default")
      (node (ref "IC3") (pin "12") (pinfunction "RCK_12") (pintype "input"))
      (node (ref "IC5") (pin "12") (pinfunction "RCK_12") (pintype "input"))
      (node (ref "R21") (pin "1") (pinfunction "1_1") (pintype "passive"))
      (node (ref "U$1") (pin "PA8") (pinfunction "PA8_PA8") (pintype "bidirectional"))
    )
    (net (code "148") (name "SCK") (class "Default")
      (node (ref "IC1") (pin "7") (pinfunction "CLK_7") (pintype "input"))
      (node (ref "IC3") (pin "11") (pinfunction "SCK_11") (pintype "input"))
      (node (ref "IC4") (pin "7") (pinfunction "CLK_7") (pintype "input"))
      (node (ref "IC5") (pin "11") (pinfunction "SCK_11") (pintype "input"))
      (node (ref "R19") (pin "1") (pinfunction "1_1") (pintype "passive"))
      (node (ref "U$1") (pin "PB3") (pinfunction "PB3_PB3") (pintype "bidirectional"))
    )
    (net (code "149") (name "SLNK1") (class "Default")
      (node (ref "IC3") (pin "14") (pinfunction "SER_14") (pintype "input"))
      (node (ref "IC5") (pin "9") (pinfunction "QH*_9") (pintype "tri_state"))
    )
    (net (code "150") (name "unconnected-(H1-MOUNT-PadB3,3)") (class "Default")
      (node (ref "H1") (pin "B3,3") (pinfunction "MOUNT_B3,3") (pintype "passive"))
    )
    (net (code "151") (name "unconnected-(H2-MOUNT-PadB3,3)") (class "Default")
      (node (ref "H2") (pin "B3,3") (pinfunction "MOUNT_B3,3") (pintype "passive"))
    )
    (net (code "152") (name "unconnected-(H3-MOUNT-PadB3,3)") (class "Default")
      (node (ref "H3") (pin "B3,3") (pinfunction "MOUNT_B3,3") (pintype "passive"))
    )
    (net (code "153") (name "unconnected-(H4-MOUNT-PadB3,3)") (class "Default")
      (node (ref "H4") (pin "B3,3") (pinfunction "MOUNT_B3,3") (pintype "passive"))
    )
    (net (code "154") (name "unconnected-(IC3A-QH*-Pad9)") (class "Default")
      (node (ref "IC3") (pin "9") (pinfunction "QH*_9") (pintype "tri_state"))
    )
    (net (code "155") (name "unconnected-(IC7-RS-Pad8)") (class "Default")
      (node (ref "IC7") (pin "8") (pinfunction "RS_8") (pintype "input"))
    )
    (net (code "156") (name "unconnected-(IC7-VREF-Pad5)") (class "Default")
      (node (ref "IC7") (pin "5") (pinfunction "VREF_5") (pintype "output"))
    )
    (net (code "157") (name "unconnected-(J3-Pad2)") (class "Default")
      (node (ref "J3") (pin "2") (pinfunction "2_2") (pintype "passive"))
    )
    (net (code "158") (name "unconnected-(JP4-Pad1)") (class "Default")
      (node (ref "JP4") (pin "1") (pinfunction "1_1") (pintype "passive"))
    )
    (net (code "159") (name "unconnected-(JP4-Pad2)") (class "Default")
      (node (ref "JP4") (pin "2") (pinfunction "2_2") (pintype "passive"))
    )
    (net (code "160") (name "unconnected-(JP4-Pad3)") (class "Default")
      (node (ref "JP4") (pin "3") (pinfunction "3_3") (pintype "passive"))
    )
    (net (code "161") (name "unconnected-(JP4-Pad4)") (class "Default")
      (node (ref "JP4") (pin "4") (pinfunction "4_4") (pintype "passive"))
    )
    (net (code "162") (name "unconnected-(JP7-Pad1)") (class "Default")
      (node (ref "JP7") (pin "1") (pinfunction "1_1") (pintype "passive"))
    )
    (net (code "163") (name "unconnected-(JP7-Pad2)") (class "Default")
      (node (ref "JP7") (pin "2") (pinfunction "2_2") (pintype "passive"))
    )
    (net (code "164") (name "unconnected-(JP7-Pad3)") (class "Default")
      (node (ref "JP7") (pin "3") (pinfunction "3_3") (pintype "passive"))
    )
    (net (code "165") (name "unconnected-(JP7-Pad4)") (class "Default")
      (node (ref "JP7") (pin "4") (pinfunction "4_4") (pintype "passive"))
    )
    (net (code "166") (name "unconnected-(JP7-Pad5)") (class "Default")
      (node (ref "JP7") (pin "5") (pinfunction "5_5") (pintype "passive"))
    )
    (net (code "167") (name "unconnected-(JP7-Pad6)") (class "Default")
      (node (ref "JP7") (pin "6") (pinfunction "6_6") (pintype "passive"))
    )
    (net (code "168") (name "unconnected-(JP8-Pad1)") (class "Default")
      (node (ref "JP8") (pin "1") (pinfunction "1_1") (pintype "passive"))
    )
    (net (code "169") (name "unconnected-(JP8-Pad2)") (class "Default")
      (node (ref "JP8") (pin "2") (pinfunction "2_2") (pintype "passive"))
    )
    (net (code "170") (name "unconnected-(JP8-Pad3)") (class "Default")
      (node (ref "JP8") (pin "3") (pinfunction "3_3") (pintype "passive"))
    )
    (net (code "171") (name "unconnected-(JP8-Pad4)") (class "Default")
      (node (ref "JP8") (pin "4") (pinfunction "4_4") (pintype "passive"))
    )
    (net (code "172") (name "unconnected-(JP9-Pad1)") (class "Default")
      (node (ref "JP9") (pin "1") (pinfunction "1_1") (pintype "passive"))
    )
    (net (code "173") (name "unconnected-(JP9-Pad2)") (class "Default")
      (node (ref "JP9") (pin "2") (pinfunction "2_2") (pintype "passive"))
    )
    (net (code "174") (name "unconnected-(JP9-Pad3)") (class "Default")
      (node (ref "JP9") (pin "3") (pinfunction "3_3") (pintype "passive"))
    )
    (net (code "175") (name "unconnected-(JP9-Pad4)") (class "Default")
      (node (ref "JP9") (pin "4") (pinfunction "4_4") (pintype "passive"))
    )
    (net (code "176") (name "unconnected-(JP10-Pad1)") (class "Default")
      (node (ref "JP10") (pin "1") (pinfunction "1_1") (pintype "passive"))
    )
    (net (code "177") (name "unconnected-(JP10-Pad2)") (class "Default")
      (node (ref "JP10") (pin "2") (pinfunction "2_2") (pintype "passive"))
    )
    (net (code "178") (name "unconnected-(JP10-Pad3)") (class "Default")
      (node (ref "JP10") (pin "3") (pinfunction "3_3") (pintype "passive"))
    )
    (net (code "179") (name "unconnected-(JP10-Pad4)") (class "Default")
      (node (ref "JP10") (pin "4") (pinfunction "4_4") (pintype "passive"))
    )
    (net (code "180") (name "unconnected-(JP11-Pad1)") (class "Default")
      (node (ref "JP11") (pin "1") (pinfunction "1_1") (pintype "passive"))
    )
    (net (code "181") (name "unconnected-(JP11-Pad2)") (class "Default")
      (node (ref "JP11") (pin "2") (pinfunction "2_2") (pintype "passive"))
    )
    (net (code "182") (name "unconnected-(JP11-Pad3)") (class "Default")
      (node (ref "JP11") (pin "3") (pinfunction "3_3") (pintype "passive"))
    )
    (net (code "183") (name "unconnected-(JP11-Pad4)") (class "Default")
      (node (ref "JP11") (pin "4") (pinfunction "4_4") (pintype "passive"))
    )
    (net (code "184") (name "unconnected-(JP11-Pad5)") (class "Default")
      (node (ref "JP11") (pin "5") (pinfunction "5_5") (pintype "passive"))
    )
    (net (code "185") (name "unconnected-(JP11-Pad6)") (class "Default")
      (node (ref "JP11") (pin "6") (pinfunction "6_6") (pintype "passive"))
    )
    (net (code "186") (name "unconnected-(JP13-Pad5)") (class "Default")
      (node (ref "JP13") (pin "5") (pinfunction "5_5") (pintype "passive"))
    )
    (net (code "187") (name "unconnected-(JP13-Pad6)") (class "Default")
      (node (ref "JP13") (pin "6") (pinfunction "6_6") (pintype "passive"))
    )
    (net (code "188") (name "unconnected-(JP14-Pad5)") (class "Default")
      (node (ref "JP14") (pin "5") (pinfunction "5_5") (pintype "passive"))
    )
    (net (code "189") (name "unconnected-(JP14-Pad6)") (class "Default")
      (node (ref "JP14") (pin "6") (pinfunction "6_6") (pintype "passive"))
    )
    (net (code "190") (name "unconnected-(JP15-Pad5)") (class "Default")
      (node (ref "JP15") (pin "5") (pinfunction "5_5") (pintype "passive"))
    )
    (net (code "191") (name "unconnected-(JP15-Pad6)") (class "Default")
      (node (ref "JP15") (pin "6") (pinfunction "6_6") (pintype "passive"))
    )
    (net (code "192") (name "unconnected-(U$1-PadBOOT0)") (class "Default")
      (node (ref "U$1") (pin "BOOT0") (pinfunction "BOOT0_BOOT0") (pintype "bidirectional"))
    )
    (net (code "193") (name "unconnected-(U$1-PadIOREF2)") (class "Default")
      (node (ref "U$1") (pin "IOREF2") (pinfunction "IOREF2_IOREF2") (pintype "input"))
    )
    (net (code "194") (name "unconnected-(U$1-PadNC1-PF7)") (class "Default")
      (node (ref "U$1") (pin "NC1-PF7") (pinfunction "NC1-PF7_NC1-PF7") (pintype "bidirectional"))
    )
    (net (code "195") (name "unconnected-(U$1-PadNC2-PF6)") (class "Default")
      (node (ref "U$1") (pin "NC2-PF6") (pinfunction "NC2-PF6_NC2-PF6") (pintype "bidirectional"))
    )
    (net (code "196") (name "unconnected-(U$1-PadNC3)") (class "Default")
      (node (ref "U$1") (pin "NC3") (pinfunction "NC3_NC3") (pintype "no_connect"))
    )
    (net (code "197") (name "unconnected-(U$1-PadNC4)") (class "Default")
      (node (ref "U$1") (pin "NC4") (pinfunction "NC4_NC4") (pintype "no_connect"))
    )
    (net (code "198") (name "unconnected-(U$1-PadNC5-PD8)") (class "Default")
      (node (ref "U$1") (pin "NC5-PD8") (pinfunction "NC5-PD8_NC5-PD8") (pintype "bidirectional"))
    )
    (net (code "199") (name "unconnected-(U$1-PadNC6-PB11)") (class "Default")
      (node (ref "U$1") (pin "NC6-PB11") (pinfunction "NC6-PB11_NC6-PB11") (pintype "no_connect"))
    )
    (net (code "200") (name "unconnected-(U$1-PadNC7-PF5)") (class "Default")
      (node (ref "U$1") (pin "NC7-PF5") (pinfunction "NC7-PF5_NC7-PF5") (pintype "bidirectional"))
    )
    (net (code "201") (name "unconnected-(U$1-PadNC8-PF4)") (class "Default")
      (node (ref "U$1") (pin "NC8-PF4") (pinfunction "NC8-PF4_NC8-PF4") (pintype "bidirectional"))
    )
    (net (code "202") (name "unconnected-(U$1-PadNRESET)") (class "Default")
      (node (ref "U$1") (pin "NRESET") (pinfunction "NRESET_NRESET") (pintype "input"))
    )
    (net (code "203") (name "unconnected-(U$1-PadPA1)") (class "Default")
      (node (ref "U$1") (pin "PA1") (pinfunction "PA1_PA1") (pintype "bidirectional"))
    )
    (net (code "204") (name "unconnected-(U$1-PadPA2)") (class "Default")
      (node (ref "U$1") (pin "PA2") (pinfunction "PA2_PA2") (pintype "bidirectional"))
    )
    (net (code "205") (name "unconnected-(U$1-PadPA3)") (class "Default")
      (node (ref "U$1") (pin "PA3") (pinfunction "PA3_PA3") (pintype "bidirectional"))
    )
    (net (code "206") (name "unconnected-(U$1-PadPA5)") (class "Default")
      (node (ref "U$1") (pin "PA5") (pinfunction "PA5_PA5") (pintype "bidirectional"))
    )
    (net (code "207") (name "unconnected-(U$1-PadPA7)") (class "Default")
      (node (ref "U$1") (pin "PA7") (pinfunction "PA7_PA7") (pintype "bidirectional"))
    )
    (net (code "208") (name "unconnected-(U$1-PadPA9)") (class "Default")
      (node (ref "U$1") (pin "PA9") (pinfunction "PA9_PA9") (pintype "bidirectional"))
    )
    (net (code "209") (name "unconnected-(U$1-PadPA10)") (class "Default")
      (node (ref "U$1") (pin "PA10") (pinfunction "PA10_PA10") (pintype "bidirectional"))
    )
    (net (code "210") (name "unconnected-(U$1-PadPA11)") (class "Default")
      (node (ref "U$1") (pin "PA11") (pinfunction "PA11_PA11") (pintype "bidirectional"))
    )
    (net (code "211") (name "unconnected-(U$1-PadPA12)") (class "Default")
      (node (ref "U$1") (pin "PA12") (pinfunction "PA12_PA12") (pintype "bidirectional"))
    )
    (net (code "212") (name "unconnected-(U$1-PadPA13)") (class "Default")
      (node (ref "U$1") (pin "PA13") (pinfunction "PA13_PA13") (pintype "bidirectional"))
    )
    (net (code "213") (name "unconnected-(U$1-PadPA14)") (class "Default")
      (node (ref "U$1") (pin "PA14") (pinfunction "PA14_PA14") (pintype "bidirectional"))
    )
    (net (code "214") (name "unconnected-(U$1-PadPB0)") (class "Default")
      (node (ref "U$1") (pin "PB0") (pinfunction "PB0_PB0") (pintype "bidirectional"))
    )
    (net (code "215") (name "unconnected-(U$1-PadPB6)") (class "Default")
      (node (ref "U$1") (pin "PB6") (pinfunction "PB6_PB6") (pintype "bidirectional"))
    )
    (net (code "216") (name "unconnected-(U$1-PadPB7)") (class "Default")
      (node (ref "U$1") (pin "PB7") (pinfunction "PB7_PB7") (pintype "bidirectional"))
    )
    (net (code "217") (name "unconnected-(U$1-PadPB13)") (class "Default")
      (node (ref "U$1") (pin "PB13") (pinfunction "PB13_PB13") (pintype "bidirectional"))
    )
    (net (code "218") (name "unconnected-(U$1-PadPB14)") (class "Default")
      (node (ref "U$1") (pin "PB14") (pinfunction "PB14_PB14") (pintype "bidirectional"))
    )
    (net (code "219") (name "unconnected-(U$1-PadPC1)") (class "Default")
      (node (ref "U$1") (pin "PC1") (pinfunction "PC1_PC1") (pintype "bidirectional"))
    )
    (net (code "220") (name "unconnected-(U$1-PadPC4)") (class "Default")
      (node (ref "U$1") (pin "PC4") (pinfunction "PC4_PC4") (pintype "bidirectional"))
    )
    (net (code "221") (name "unconnected-(U$1-PadPC5)") (class "Default")
      (node (ref "U$1") (pin "PC5") (pinfunction "PC5_PC5") (pintype "bidirectional"))
    )
    (net (code "222") (name "unconnected-(U$1-PadPC6)") (class "Default")
      (node (ref "U$1") (pin "PC6") (pinfunction "PC6_PC6") (pintype "bidirectional"))
    )
    (net (code "223") (name "unconnected-(U$1-PadPC7)") (class "Default")
      (node (ref "U$1") (pin "PC7") (pinfunction "PC7_PC7") (pintype "bidirectional"))
    )
    (net (code "224") (name "unconnected-(U$1-PadPC8)") (class "Default")
      (node (ref "U$1") (pin "PC8") (pinfunction "PC8_PC8") (pintype "bidirectional"))
    )
    (net (code "225") (name "unconnected-(U$1-PadPC9)") (class "Default")
      (node (ref "U$1") (pin "PC9") (pinfunction "PC9_PC9") (pintype "bidirectional"))
    )
    (net (code "226") (name "unconnected-(U$1-PadPC13)") (class "Default")
      (node (ref "U$1") (pin "PC13") (pinfunction "PC13_PC13") (pintype "bidirectional"))
    )
    (net (code "227") (name "unconnected-(U$1-PadPC14)") (class "Default")
      (node (ref "U$1") (pin "PC14") (pinfunction "PC14_PC14") (pintype "bidirectional"))
    )
    (net (code "228") (name "unconnected-(U$1-PadPC15)") (class "Default")
      (node (ref "U$1") (pin "PC15") (pinfunction "PC15_PC15") (pintype "bidirectional"))
    )
    (net (code "229") (name "unconnected-(U$1-PadPF0-PH0)") (class "Default")
      (node (ref "U$1") (pin "PF0-PH0") (pinfunction "PF0-PH0_PF0-PH0") (pintype "bidirectional"))
    )
  )
)
